# altair.net
KiCad netlist of a schematic drawn in EAGLE
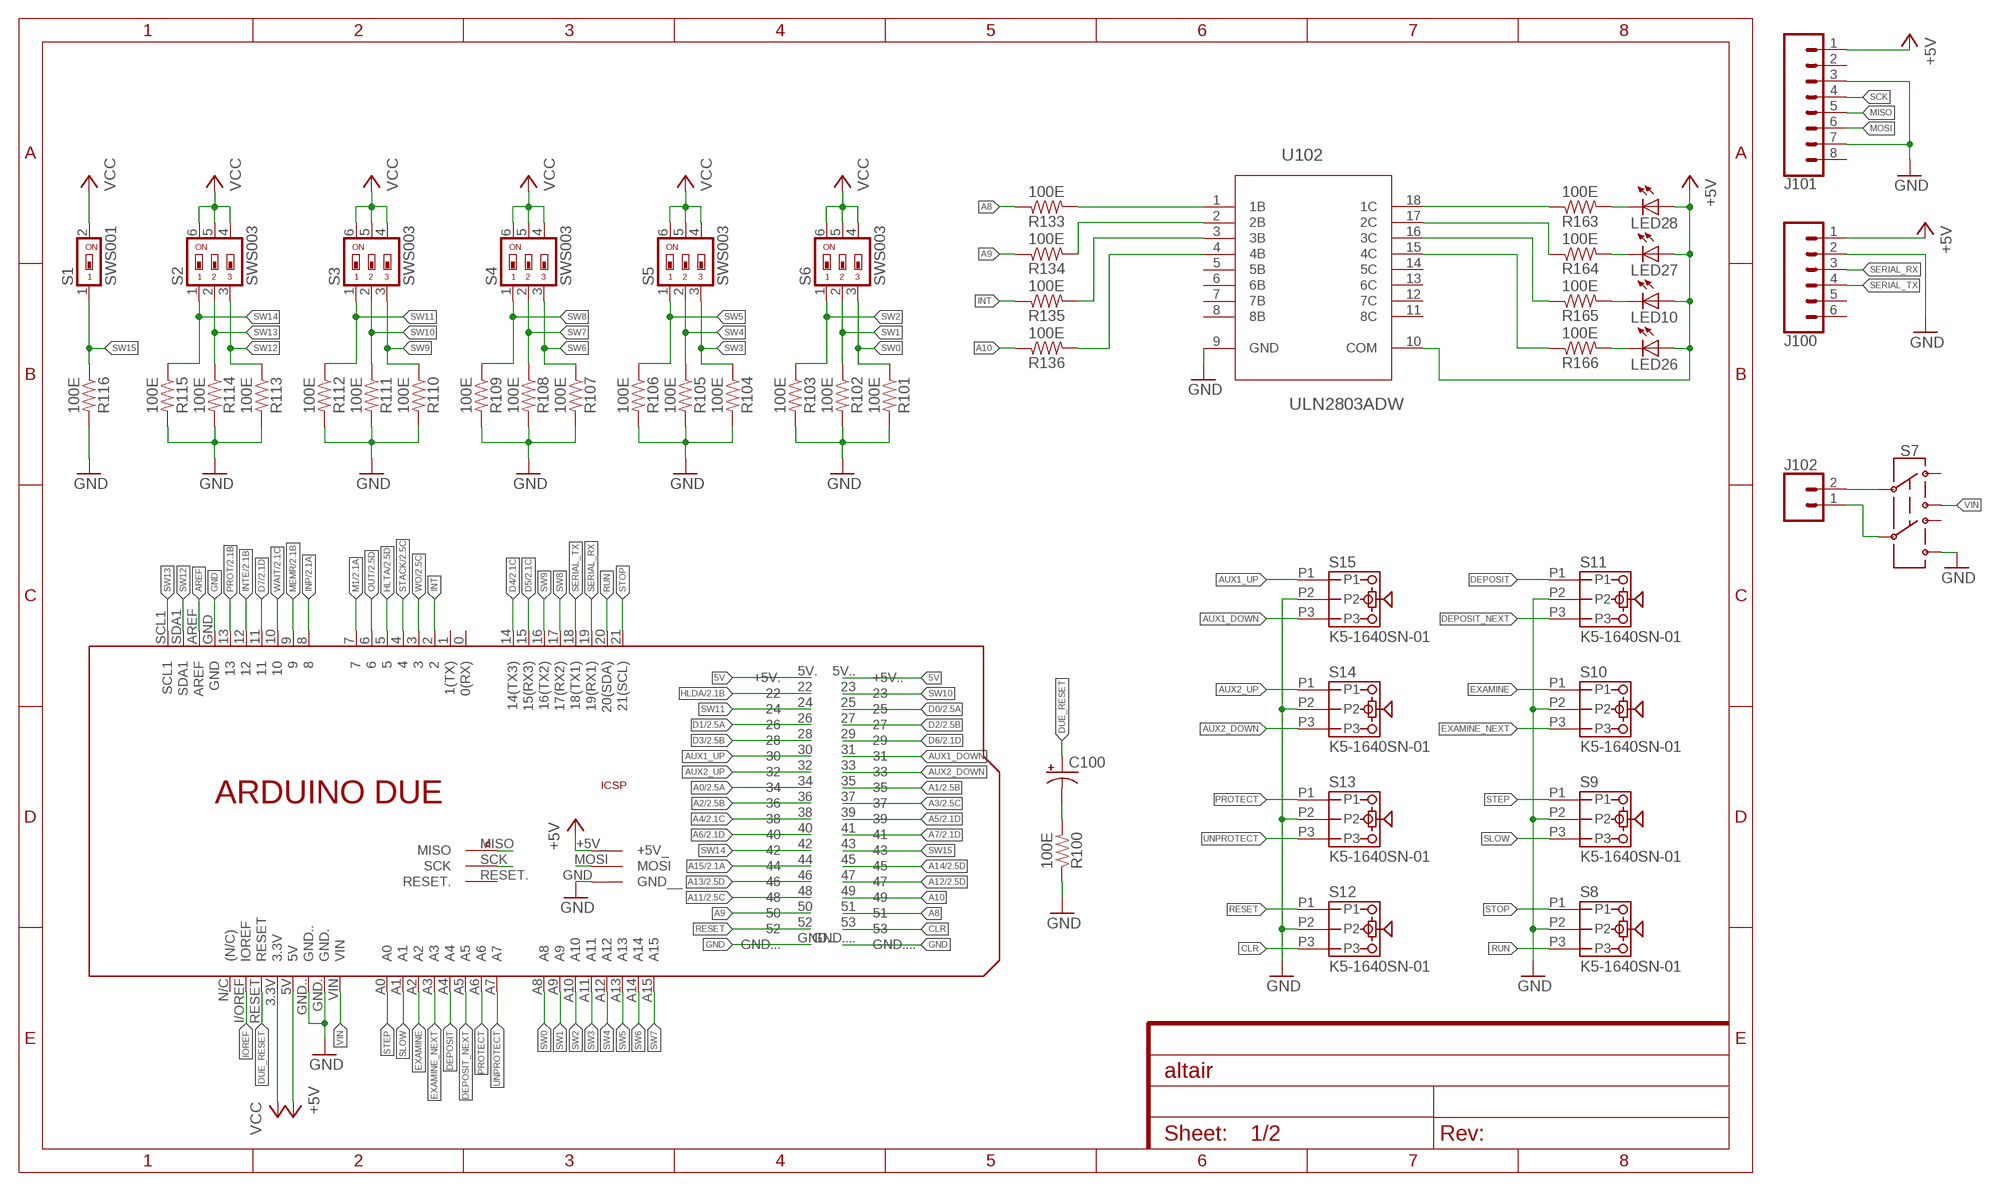
[diagram p0: schematic, sheet 1]
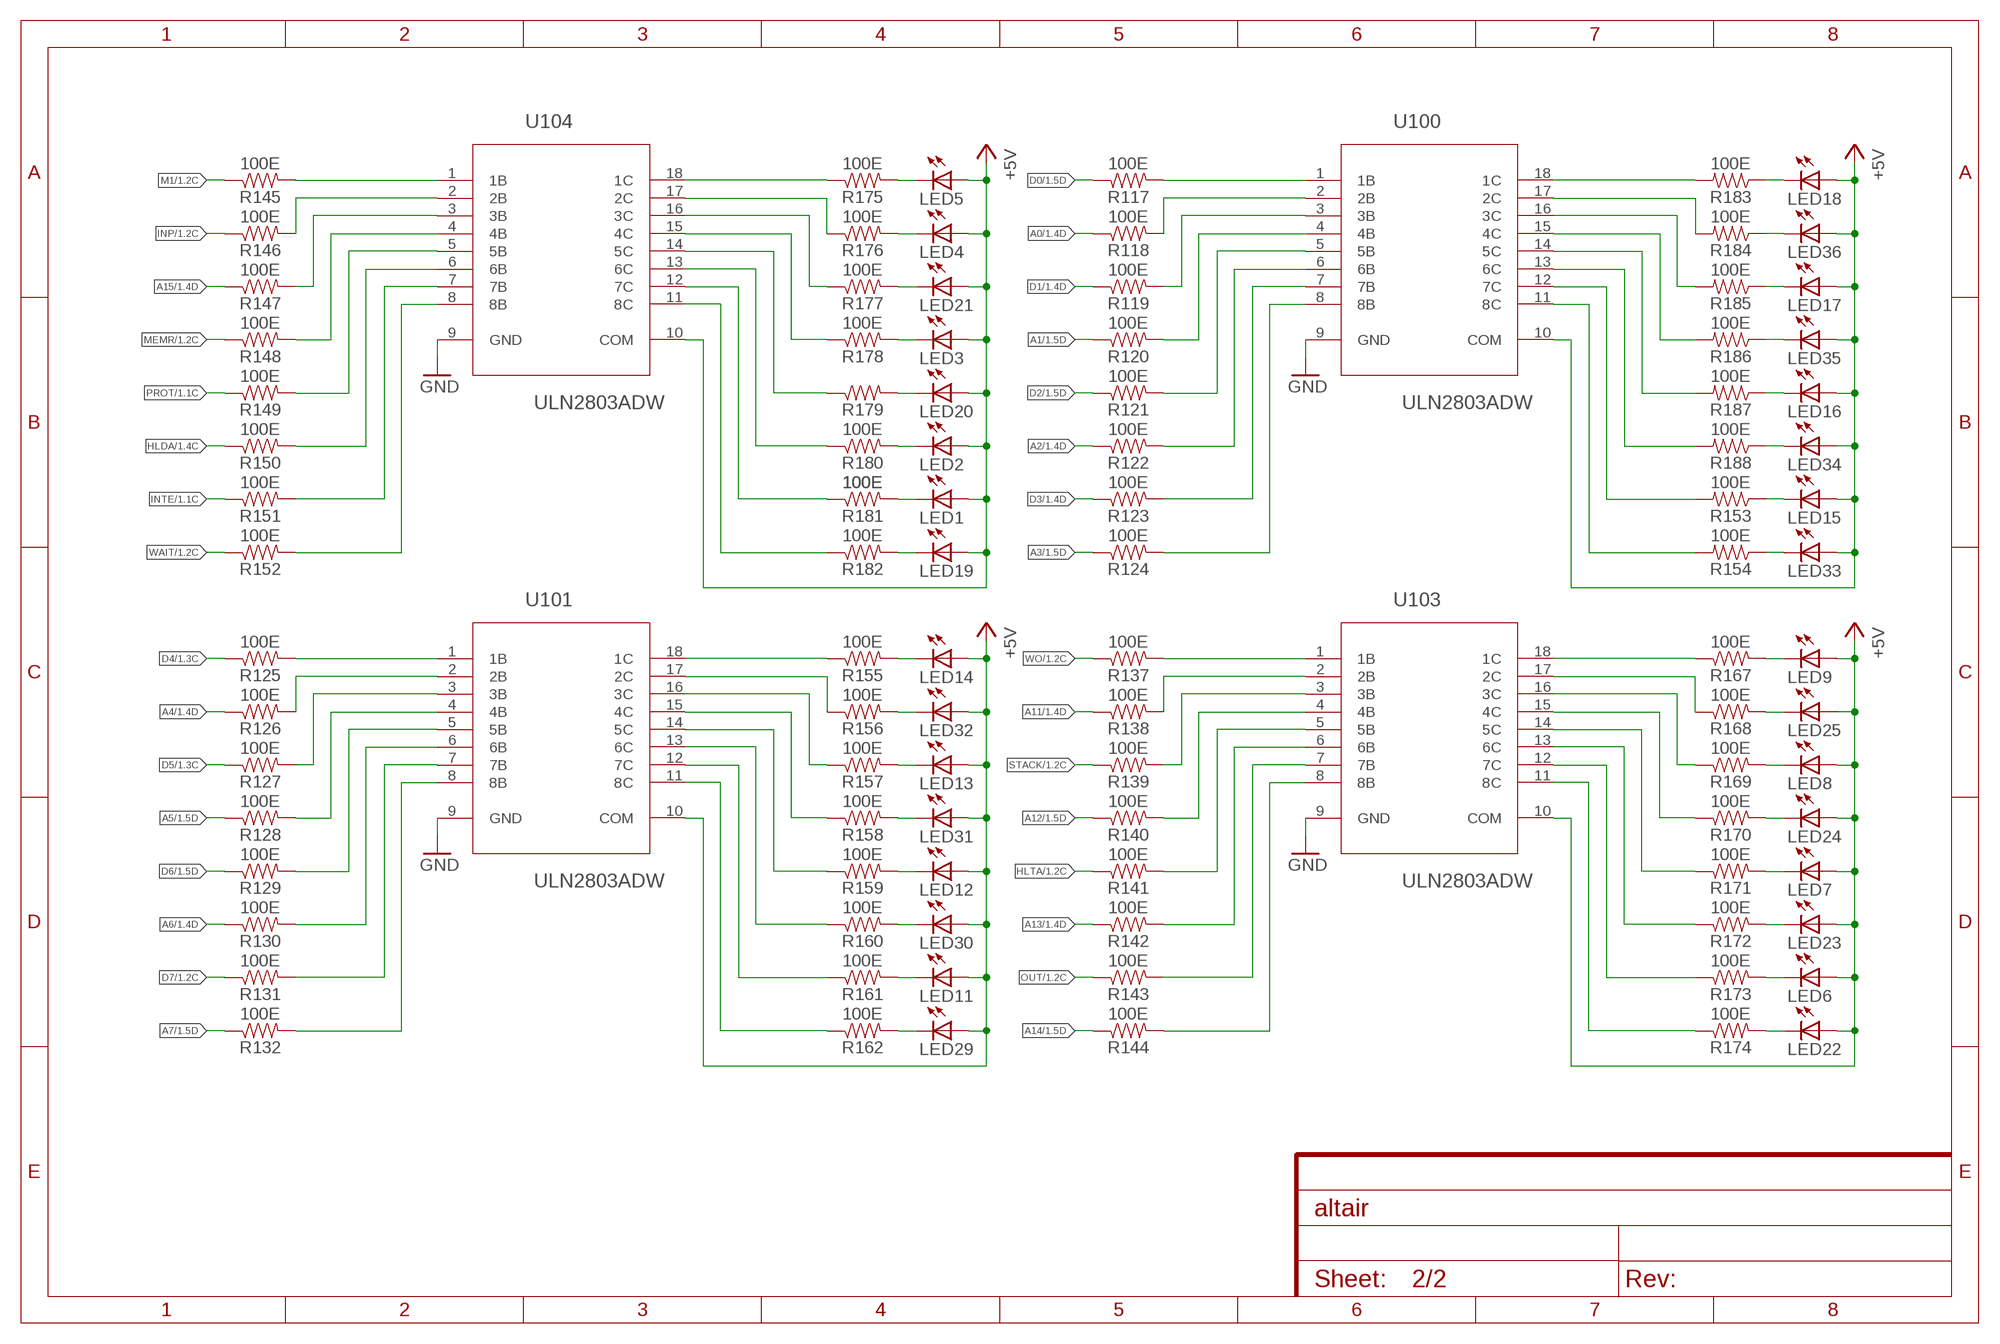
[diagram p1: schematic, sheet 2]

(export (version "E")
  (design (tool "Eeschema 10.0.6"))
  (components
    (comp (ref "C100")
      (value "CPOL-USD")
      (footprint "eagle-import:PANASONIC_D")
      (libsource (lib "eagle-import") (part "CPOL-USD"))
    )
    (comp (ref "J100")
      (value "CONN_06LOCK")
      (footprint "eagle-import:1X06_LOCK")
      (libsource (lib "eagle-import") (part "CONN_06LOCK"))
    )
    (comp (ref "J101")
      (value "CONN_08LOCK")
      (footprint "eagle-import:1X08_LOCK")
      (libsource (lib "eagle-import") (part "CONN_08LOCK"))
    )
    (comp (ref "J102")
      (value "CONN_02POLAR_LOCK")
      (footprint "eagle-import:MOLEX-1X2_LOCK")
      (libsource (lib "eagle-import") (part "CONN_02POLAR_LOCK"))
    )
    (comp (ref "LED10")
      (value "LEDCHIP-LED0805")
      (footprint "eagle-import:CHIP-LED0805")
      (libsource (lib "eagle-import") (part "LEDCHIP-LED0805"))
    )
    (comp (ref "LED26")
      (value "LEDCHIP-LED0805")
      (footprint "eagle-import:CHIP-LED0805")
      (libsource (lib "eagle-import") (part "LEDCHIP-LED0805"))
    )
    (comp (ref "LED27")
      (value "LEDCHIP-LED0805")
      (footprint "eagle-import:CHIP-LED0805")
      (libsource (lib "eagle-import") (part "LEDCHIP-LED0805"))
    )
    (comp (ref "LED28")
      (value "LEDCHIP-LED0805")
      (footprint "eagle-import:CHIP-LED0805")
      (libsource (lib "eagle-import") (part "LEDCHIP-LED0805"))
    )
    (comp (ref "PCB1")
      (value "ARDUINO_DUEARDUINO_DUE")
      (footprint "eagle-import:ARDUINO_MEGA2560")
      (libsource (lib "eagle-import") (part "ARDUINO_DUEARDUINO_DUE"))
    )
    (comp (ref "R100")
      (value "100E")
      (footprint "eagle-import:0805")
      (libsource (lib "eagle-import") (part "RESISTOR0805"))
    )
    (comp (ref "R101")
      (value "100E")
      (footprint "eagle-import:0805")
      (libsource (lib "eagle-import") (part "RESISTOR0805"))
    )
    (comp (ref "R102")
      (value "100E")
      (footprint "eagle-import:0805")
      (libsource (lib "eagle-import") (part "RESISTOR0805"))
    )
    (comp (ref "R103")
      (value "100E")
      (footprint "eagle-import:0805")
      (libsource (lib "eagle-import") (part "RESISTOR0805"))
    )
    (comp (ref "R104")
      (value "100E")
      (footprint "eagle-import:0805")
      (libsource (lib "eagle-import") (part "RESISTOR0805"))
    )
    (comp (ref "R105")
      (value "100E")
      (footprint "eagle-import:0805")
      (libsource (lib "eagle-import") (part "RESISTOR0805"))
    )
    (comp (ref "R106")
      (value "100E")
      (footprint "eagle-import:0805")
      (libsource (lib "eagle-import") (part "RESISTOR0805"))
    )
    (comp (ref "R107")
      (value "100E")
      (footprint "eagle-import:0805")
      (libsource (lib "eagle-import") (part "RESISTOR0805"))
    )
    (comp (ref "R108")
      (value "100E")
      (footprint "eagle-import:0805")
      (libsource (lib "eagle-import") (part "RESISTOR0805"))
    )
    (comp (ref "R109")
      (value "100E")
      (footprint "eagle-import:0805")
      (libsource (lib "eagle-import") (part "RESISTOR0805"))
    )
    (comp (ref "R110")
      (value "100E")
      (footprint "eagle-import:0805")
      (libsource (lib "eagle-import") (part "RESISTOR0805"))
    )
    (comp (ref "R111")
      (value "100E")
      (footprint "eagle-import:0805")
      (libsource (lib "eagle-import") (part "RESISTOR0805"))
    )
    (comp (ref "R112")
      (value "100E")
      (footprint "eagle-import:0805")
      (libsource (lib "eagle-import") (part "RESISTOR0805"))
    )
    (comp (ref "R113")
      (value "100E")
      (footprint "eagle-import:0805")
      (libsource (lib "eagle-import") (part "RESISTOR0805"))
    )
    (comp (ref "R114")
      (value "100E")
      (footprint "eagle-import:0805")
      (libsource (lib "eagle-import") (part "RESISTOR0805"))
    )
    (comp (ref "R115")
      (value "100E")
      (footprint "eagle-import:0805")
      (libsource (lib "eagle-import") (part "RESISTOR0805"))
    )
    (comp (ref "R116")
      (value "100E")
      (footprint "eagle-import:0805")
      (libsource (lib "eagle-import") (part "RESISTOR0805"))
    )
    (comp (ref "R133")
      (value "100E")
      (footprint "eagle-import:0805")
      (libsource (lib "eagle-import") (part "RESISTOR0805"))
    )
    (comp (ref "R134")
      (value "100E")
      (footprint "eagle-import:0805")
      (libsource (lib "eagle-import") (part "RESISTOR0805"))
    )
    (comp (ref "R135")
      (value "100E")
      (footprint "eagle-import:0805")
      (libsource (lib "eagle-import") (part "RESISTOR0805"))
    )
    (comp (ref "R136")
      (value "100E")
      (footprint "eagle-import:0805")
      (libsource (lib "eagle-import") (part "RESISTOR0805"))
    )
    (comp (ref "R163")
      (value "100E")
      (footprint "eagle-import:0805")
      (libsource (lib "eagle-import") (part "RESISTOR0805"))
    )
    (comp (ref "R164")
      (value "100E")
      (footprint "eagle-import:0805")
      (libsource (lib "eagle-import") (part "RESISTOR0805"))
    )
    (comp (ref "R165")
      (value "100E")
      (footprint "eagle-import:0805")
      (libsource (lib "eagle-import") (part "RESISTOR0805"))
    )
    (comp (ref "R166")
      (value "100E")
      (footprint "eagle-import:0805")
      (libsource (lib "eagle-import") (part "RESISTOR0805"))
    )
    (comp (ref "S1")
      (value "SWS001")
      (footprint "eagle-import:SMS-001")
      (libsource (lib "eagle-import") (part "SWS001"))
    )
    (comp (ref "S2")
      (value "SWS003")
      (footprint "eagle-import:SMS-003")
      (libsource (lib "eagle-import") (part "SWS003"))
    )
    (comp (ref "S3")
      (value "SWS003")
      (footprint "eagle-import:SMS-003")
      (libsource (lib "eagle-import") (part "SWS003"))
    )
    (comp (ref "S4")
      (value "SWS003")
      (footprint "eagle-import:SMS-003")
      (libsource (lib "eagle-import") (part "SWS003"))
    )
    (comp (ref "S5")
      (value "SWS003")
      (footprint "eagle-import:SMS-003")
      (libsource (lib "eagle-import") (part "SWS003"))
    )
    (comp (ref "S6")
      (value "SWS003")
      (footprint "eagle-import:SMS-003")
      (libsource (lib "eagle-import") (part "SWS003"))
    )
    (comp (ref "S7")
      (value "SWITCH-DPDT-SMD-AYZ0202")
      (footprint "eagle-import:SWITCH_DPDT_SMD_AYZ0202")
      (libsource (lib "eagle-import") (part "SWITCH-DPDT-SMD-AYZ0202"))
    )
    (comp (ref "S8")
      (value "K5-1640SN-01")
      (footprint "eagle-import:K5-1640SN-01")
      (libsource (lib "eagle-import") (part "K5-1640SN-01"))
    )
    (comp (ref "S9")
      (value "K5-1640SN-01")
      (footprint "eagle-import:K5-1640SN-01")
      (libsource (lib "eagle-import") (part "K5-1640SN-01"))
    )
    (comp (ref "S10")
      (value "K5-1640SN-01")
      (footprint "eagle-import:K5-1640SN-01")
      (libsource (lib "eagle-import") (part "K5-1640SN-01"))
    )
    (comp (ref "S11")
      (value "K5-1640SN-01")
      (footprint "eagle-import:K5-1640SN-01")
      (libsource (lib "eagle-import") (part "K5-1640SN-01"))
    )
    (comp (ref "S12")
      (value "K5-1640SN-01")
      (footprint "eagle-import:K5-1640SN-01")
      (libsource (lib "eagle-import") (part "K5-1640SN-01"))
    )
    (comp (ref "S13")
      (value "K5-1640SN-01")
      (footprint "eagle-import:K5-1640SN-01")
      (libsource (lib "eagle-import") (part "K5-1640SN-01"))
    )
    (comp (ref "S14")
      (value "K5-1640SN-01")
      (footprint "eagle-import:K5-1640SN-01")
      (libsource (lib "eagle-import") (part "K5-1640SN-01"))
    )
    (comp (ref "S15")
      (value "K5-1640SN-01")
      (footprint "eagle-import:K5-1640SN-01")
      (libsource (lib "eagle-import") (part "K5-1640SN-01"))
    )
    (comp (ref "U102")
      (value "ULN2803ADW")
      (footprint "eagle-import:SOIC127P1030X265-18N")
      (libsource (lib "eagle-import") (part "ULN2803ADW"))
    )
    (comp (ref "LED1")
      (value "LEDCHIP-LED0805")
      (footprint "eagle-import:CHIP-LED0805")
      (libsource (lib "eagle-import") (part "LEDCHIP-LED0805"))
    )
    (comp (ref "LED2")
      (value "LEDCHIP-LED0805")
      (footprint "eagle-import:CHIP-LED0805")
      (libsource (lib "eagle-import") (part "LEDCHIP-LED0805"))
    )
    (comp (ref "LED3")
      (value "LEDCHIP-LED0805")
      (footprint "eagle-import:CHIP-LED0805")
      (libsource (lib "eagle-import") (part "LEDCHIP-LED0805"))
    )
    (comp (ref "LED4")
      (value "LEDCHIP-LED0805")
      (footprint "eagle-import:CHIP-LED0805")
      (libsource (lib "eagle-import") (part "LEDCHIP-LED0805"))
    )
    (comp (ref "LED5")
      (value "LEDCHIP-LED0805")
      (footprint "eagle-import:CHIP-LED0805")
      (libsource (lib "eagle-import") (part "LEDCHIP-LED0805"))
    )
    (comp (ref "LED6")
      (value "LEDCHIP-LED0805")
      (footprint "eagle-import:CHIP-LED0805")
      (libsource (lib "eagle-import") (part "LEDCHIP-LED0805"))
    )
    (comp (ref "LED7")
      (value "LEDCHIP-LED0805")
      (footprint "eagle-import:CHIP-LED0805")
      (libsource (lib "eagle-import") (part "LEDCHIP-LED0805"))
    )
    (comp (ref "LED8")
      (value "LEDCHIP-LED0805")
      (footprint "eagle-import:CHIP-LED0805")
      (libsource (lib "eagle-import") (part "LEDCHIP-LED0805"))
    )
    (comp (ref "LED9")
      (value "LEDCHIP-LED0805")
      (footprint "eagle-import:CHIP-LED0805")
      (libsource (lib "eagle-import") (part "LEDCHIP-LED0805"))
    )
    (comp (ref "LED11")
      (value "LEDCHIP-LED0805")
      (footprint "eagle-import:CHIP-LED0805")
      (libsource (lib "eagle-import") (part "LEDCHIP-LED0805"))
    )
    (comp (ref "LED12")
      (value "LEDCHIP-LED0805")
      (footprint "eagle-import:CHIP-LED0805")
      (libsource (lib "eagle-import") (part "LEDCHIP-LED0805"))
    )
    (comp (ref "LED13")
      (value "LEDCHIP-LED0805")
      (footprint "eagle-import:CHIP-LED0805")
      (libsource (lib "eagle-import") (part "LEDCHIP-LED0805"))
    )
    (comp (ref "LED14")
      (value "LEDCHIP-LED0805")
      (footprint "eagle-import:CHIP-LED0805")
      (libsource (lib "eagle-import") (part "LEDCHIP-LED0805"))
    )
    (comp (ref "LED15")
      (value "LEDCHIP-LED0805")
      (footprint "eagle-import:CHIP-LED0805")
      (libsource (lib "eagle-import") (part "LEDCHIP-LED0805"))
    )
    (comp (ref "LED16")
      (value "LEDCHIP-LED0805")
      (footprint "eagle-import:CHIP-LED0805")
      (libsource (lib "eagle-import") (part "LEDCHIP-LED0805"))
    )
    (comp (ref "LED17")
      (value "LEDCHIP-LED0805")
      (footprint "eagle-import:CHIP-LED0805")
      (libsource (lib "eagle-import") (part "LEDCHIP-LED0805"))
    )
    (comp (ref "LED18")
      (value "LEDCHIP-LED0805")
      (footprint "eagle-import:CHIP-LED0805")
      (libsource (lib "eagle-import") (part "LEDCHIP-LED0805"))
    )
    (comp (ref "LED19")
      (value "LEDCHIP-LED0805")
      (footprint "eagle-import:CHIP-LED0805")
      (libsource (lib "eagle-import") (part "LEDCHIP-LED0805"))
    )
    (comp (ref "LED20")
      (value "LEDCHIP-LED0805")
      (footprint "eagle-import:CHIP-LED0805")
      (libsource (lib "eagle-import") (part "LEDCHIP-LED0805"))
    )
    (comp (ref "LED21")
      (value "LEDCHIP-LED0805")
      (footprint "eagle-import:CHIP-LED0805")
      (libsource (lib "eagle-import") (part "LEDCHIP-LED0805"))
    )
    (comp (ref "LED22")
      (value "LEDCHIP-LED0805")
      (footprint "eagle-import:CHIP-LED0805")
      (libsource (lib "eagle-import") (part "LEDCHIP-LED0805"))
    )
    (comp (ref "LED23")
      (value "LEDCHIP-LED0805")
      (footprint "eagle-import:CHIP-LED0805")
      (libsource (lib "eagle-import") (part "LEDCHIP-LED0805"))
    )
    (comp (ref "LED24")
      (value "LEDCHIP-LED0805")
      (footprint "eagle-import:CHIP-LED0805")
      (libsource (lib "eagle-import") (part "LEDCHIP-LED0805"))
    )
    (comp (ref "LED25")
      (value "LEDCHIP-LED0805")
      (footprint "eagle-import:CHIP-LED0805")
      (libsource (lib "eagle-import") (part "LEDCHIP-LED0805"))
    )
    (comp (ref "LED29")
      (value "LEDCHIP-LED0805")
      (footprint "eagle-import:CHIP-LED0805")
      (libsource (lib "eagle-import") (part "LEDCHIP-LED0805"))
    )
    (comp (ref "LED30")
      (value "LEDCHIP-LED0805")
      (footprint "eagle-import:CHIP-LED0805")
      (libsource (lib "eagle-import") (part "LEDCHIP-LED0805"))
    )
    (comp (ref "LED31")
      (value "LEDCHIP-LED0805")
      (footprint "eagle-import:CHIP-LED0805")
      (libsource (lib "eagle-import") (part "LEDCHIP-LED0805"))
    )
    (comp (ref "LED32")
      (value "LEDCHIP-LED0805")
      (footprint "eagle-import:CHIP-LED0805")
      (libsource (lib "eagle-import") (part "LEDCHIP-LED0805"))
    )
    (comp (ref "LED33")
      (value "LEDCHIP-LED0805")
      (footprint "eagle-import:CHIP-LED0805")
      (libsource (lib "eagle-import") (part "LEDCHIP-LED0805"))
    )
    (comp (ref "LED34")
      (value "LEDCHIP-LED0805")
      (footprint "eagle-import:CHIP-LED0805")
      (libsource (lib "eagle-import") (part "LEDCHIP-LED0805"))
    )
    (comp (ref "LED35")
      (value "LEDCHIP-LED0805")
      (footprint "eagle-import:CHIP-LED0805")
      (libsource (lib "eagle-import") (part "LEDCHIP-LED0805"))
    )
    (comp (ref "LED36")
      (value "LEDCHIP-LED0805")
      (footprint "eagle-import:CHIP-LED0805")
      (libsource (lib "eagle-import") (part "LEDCHIP-LED0805"))
    )
    (comp (ref "R117")
      (value "100E")
      (footprint "eagle-import:0805")
      (libsource (lib "eagle-import") (part "RESISTOR0805"))
    )
    (comp (ref "R118")
      (value "100E")
      (footprint "eagle-import:0805")
      (libsource (lib "eagle-import") (part "RESISTOR0805"))
    )
    (comp (ref "R119")
      (value "100E")
      (footprint "eagle-import:0805")
      (libsource (lib "eagle-import") (part "RESISTOR0805"))
    )
    (comp (ref "R120")
      (value "100E")
      (footprint "eagle-import:0805")
      (libsource (lib "eagle-import") (part "RESISTOR0805"))
    )
    (comp (ref "R121")
      (value "100E")
      (footprint "eagle-import:0805")
      (libsource (lib "eagle-import") (part "RESISTOR0805"))
    )
    (comp (ref "R122")
      (value "100E")
      (footprint "eagle-import:0805")
      (libsource (lib "eagle-import") (part "RESISTOR0805"))
    )
    (comp (ref "R123")
      (value "100E")
      (footprint "eagle-import:0805")
      (libsource (lib "eagle-import") (part "RESISTOR0805"))
    )
    (comp (ref "R124")
      (value "100E")
      (footprint "eagle-import:0805")
      (libsource (lib "eagle-import") (part "RESISTOR0805"))
    )
    (comp (ref "R125")
      (value "100E")
      (footprint "eagle-import:0805")
      (libsource (lib "eagle-import") (part "RESISTOR0805"))
    )
    (comp (ref "R126")
      (value "100E")
      (footprint "eagle-import:0805")
      (libsource (lib "eagle-import") (part "RESISTOR0805"))
    )
    (comp (ref "R127")
      (value "100E")
      (footprint "eagle-import:0805")
      (libsource (lib "eagle-import") (part "RESISTOR0805"))
    )
    (comp (ref "R128")
      (value "100E")
      (footprint "eagle-import:0805")
      (libsource (lib "eagle-import") (part "RESISTOR0805"))
    )
    (comp (ref "R129")
      (value "100E")
      (footprint "eagle-import:0805")
      (libsource (lib "eagle-import") (part "RESISTOR0805"))
    )
    (comp (ref "R130")
      (value "100E")
      (footprint "eagle-import:0805")
      (libsource (lib "eagle-import") (part "RESISTOR0805"))
    )
    (comp (ref "R131")
      (value "100E")
      (footprint "eagle-import:0805")
      (libsource (lib "eagle-import") (part "RESISTOR0805"))
    )
    (comp (ref "R132")
      (value "100E")
      (footprint "eagle-import:0805")
      (libsource (lib "eagle-import") (part "RESISTOR0805"))
    )
    (comp (ref "R137")
      (value "100E")
      (footprint "eagle-import:0805")
      (libsource (lib "eagle-import") (part "RESISTOR0805"))
    )
    (comp (ref "R138")
      (value "100E")
      (footprint "eagle-import:0805")
      (libsource (lib "eagle-import") (part "RESISTOR0805"))
    )
    (comp (ref "R139")
      (value "100E")
      (footprint "eagle-import:0805")
      (libsource (lib "eagle-import") (part "RESISTOR0805"))
    )
    (comp (ref "R140")
      (value "100E")
      (footprint "eagle-import:0805")
      (libsource (lib "eagle-import") (part "RESISTOR0805"))
    )
    (comp (ref "R141")
      (value "100E")
      (footprint "eagle-import:0805")
      (libsource (lib "eagle-import") (part "RESISTOR0805"))
    )
    (comp (ref "R142")
      (value "100E")
      (footprint "eagle-import:0805")
      (libsource (lib "eagle-import") (part "RESISTOR0805"))
    )
    (comp (ref "R143")
      (value "100E")
      (footprint "eagle-import:0805")
      (libsource (lib "eagle-import") (part "RESISTOR0805"))
    )
    (comp (ref "R144")
      (value "100E")
      (footprint "eagle-import:0805")
      (libsource (lib "eagle-import") (part "RESISTOR0805"))
    )
    (comp (ref "R145")
      (value "100E")
      (footprint "eagle-import:0805")
      (libsource (lib "eagle-import") (part "RESISTOR0805"))
    )
    (comp (ref "R146")
      (value "100E")
      (footprint "eagle-import:0805")
      (libsource (lib "eagle-import") (part "RESISTOR0805"))
    )
    (comp (ref "R147")
      (value "100E")
      (footprint "eagle-import:0805")
      (libsource (lib "eagle-import") (part "RESISTOR0805"))
    )
    (comp (ref "R148")
      (value "100E")
      (footprint "eagle-import:0805")
      (libsource (lib "eagle-import") (part "RESISTOR0805"))
    )
    (comp (ref "R149")
      (value "100E")
      (footprint "eagle-import:0805")
      (libsource (lib "eagle-import") (part "RESISTOR0805"))
    )
    (comp (ref "R150")
      (value "100E")
      (footprint "eagle-import:0805")
      (libsource (lib "eagle-import") (part "RESISTOR0805"))
    )
    (comp (ref "R151")
      (value "100E")
      (footprint "eagle-import:0805")
      (libsource (lib "eagle-import") (part "RESISTOR0805"))
    )
    (comp (ref "R152")
      (value "100E")
      (footprint "eagle-import:0805")
      (libsource (lib "eagle-import") (part "RESISTOR0805"))
    )
    (comp (ref "R153")
      (value "100E")
      (footprint "eagle-import:0805")
      (libsource (lib "eagle-import") (part "RESISTOR0805"))
    )
    (comp (ref "R154")
      (value "100E")
      (footprint "eagle-import:0805")
      (libsource (lib "eagle-import") (part "RESISTOR0805"))
    )
    (comp (ref "R155")
      (value "100E")
      (footprint "eagle-import:0805")
      (libsource (lib "eagle-import") (part "RESISTOR0805"))
    )
    (comp (ref "R156")
      (value "100E")
      (footprint "eagle-import:0805")
      (libsource (lib "eagle-import") (part "RESISTOR0805"))
    )
    (comp (ref "R157")
      (value "100E")
      (footprint "eagle-import:0805")
      (libsource (lib "eagle-import") (part "RESISTOR0805"))
    )
    (comp (ref "R158")
      (value "100E")
      (footprint "eagle-import:0805")
      (libsource (lib "eagle-import") (part "RESISTOR0805"))
    )
    (comp (ref "R159")
      (value "100E")
      (footprint "eagle-import:0805")
      (libsource (lib "eagle-import") (part "RESISTOR0805"))
    )
    (comp (ref "R160")
      (value "100E")
      (footprint "eagle-import:0805")
      (libsource (lib "eagle-import") (part "RESISTOR0805"))
    )
    (comp (ref "R161")
      (value "100E")
      (footprint "eagle-import:0805")
      (libsource (lib "eagle-import") (part "RESISTOR0805"))
    )
    (comp (ref "R162")
      (value "100E")
      (footprint "eagle-import:0805")
      (libsource (lib "eagle-import") (part "RESISTOR0805"))
    )
    (comp (ref "R167")
      (value "100E")
      (footprint "eagle-import:0805")
      (libsource (lib "eagle-import") (part "RESISTOR0805"))
    )
    (comp (ref "R168")
      (value "100E")
      (footprint "eagle-import:0805")
      (libsource (lib "eagle-import") (part "RESISTOR0805"))
    )
    (comp (ref "R169")
      (value "100E")
      (footprint "eagle-import:0805")
      (libsource (lib "eagle-import") (part "RESISTOR0805"))
    )
    (comp (ref "R170")
      (value "100E")
      (footprint "eagle-import:0805")
      (libsource (lib "eagle-import") (part "RESISTOR0805"))
    )
    (comp (ref "R171")
      (value "100E")
      (footprint "eagle-import:0805")
      (libsource (lib "eagle-import") (part "RESISTOR0805"))
    )
    (comp (ref "R172")
      (value "100E")
      (footprint "eagle-import:0805")
      (libsource (lib "eagle-import") (part "RESISTOR0805"))
    )
    (comp (ref "R173")
      (value "100E")
      (footprint "eagle-import:0805")
      (libsource (lib "eagle-import") (part "RESISTOR0805"))
    )
    (comp (ref "R174")
      (value "100E")
      (footprint "eagle-import:0805")
      (libsource (lib "eagle-import") (part "RESISTOR0805"))
    )
    (comp (ref "R175")
      (value "100E")
      (footprint "eagle-import:0805")
      (libsource (lib "eagle-import") (part "RESISTOR0805"))
    )
    (comp (ref "R176")
      (value "100E")
      (footprint "eagle-import:0805")
      (libsource (lib "eagle-import") (part "RESISTOR0805"))
    )
    (comp (ref "R177")
      (value "100E")
      (footprint "eagle-import:0805")
      (libsource (lib "eagle-import") (part "RESISTOR0805"))
    )
    (comp (ref "R178")
      (value "100E")
      (footprint "eagle-import:0805")
      (libsource (lib "eagle-import") (part "RESISTOR0805"))
    )
    (comp (ref "R179")
      (value "100E")
      (footprint "eagle-import:0805")
      (libsource (lib "eagle-import") (part "RESISTOR0805"))
    )
    (comp (ref "R180")
      (value "100E")
      (footprint "eagle-import:0805")
      (libsource (lib "eagle-import") (part "RESISTOR0805"))
    )
    (comp (ref "R181")
      (value "100E")
      (footprint "eagle-import:0805")
      (libsource (lib "eagle-import") (part "RESISTOR0805"))
    )
    (comp (ref "R182")
      (value "100E")
      (footprint "eagle-import:0805")
      (libsource (lib "eagle-import") (part "RESISTOR0805"))
    )
    (comp (ref "R183")
      (value "100E")
      (footprint "eagle-import:0805")
      (libsource (lib "eagle-import") (part "RESISTOR0805"))
    )
    (comp (ref "R184")
      (value "100E")
      (footprint "eagle-import:0805")
      (libsource (lib "eagle-import") (part "RESISTOR0805"))
    )
    (comp (ref "R185")
      (value "100E")
      (footprint "eagle-import:0805")
      (libsource (lib "eagle-import") (part "RESISTOR0805"))
    )
    (comp (ref "R186")
      (value "100E")
      (footprint "eagle-import:0805")
      (libsource (lib "eagle-import") (part "RESISTOR0805"))
    )
    (comp (ref "R187")
      (value "100E")
      (footprint "eagle-import:0805")
      (libsource (lib "eagle-import") (part "RESISTOR0805"))
    )
    (comp (ref "R188")
      (value "100E")
      (footprint "eagle-import:0805")
      (libsource (lib "eagle-import") (part "RESISTOR0805"))
    )
    (comp (ref "U100")
      (value "ULN2803ADW")
      (footprint "eagle-import:SOIC127P1030X265-18N")
      (libsource (lib "eagle-import") (part "ULN2803ADW"))
    )
    (comp (ref "U101")
      (value "ULN2803ADW")
      (footprint "eagle-import:SOIC127P1030X265-18N")
      (libsource (lib "eagle-import") (part "ULN2803ADW"))
    )
    (comp (ref "U103")
      (value "ULN2803ADW")
      (footprint "eagle-import:SOIC127P1030X265-18N")
      (libsource (lib "eagle-import") (part "ULN2803ADW"))
    )
    (comp (ref "U104")
      (value "ULN2803ADW")
      (footprint "eagle-import:SOIC127P1030X265-18N")
      (libsource (lib "eagle-import") (part "ULN2803ADW"))
    )
  )
  (nets
    (net (code "1") (name "+5V") (class "Default")
      (node (ref "J100") (pin "1") (pinfunction "1_1") (pintype "passive"))
      (node (ref "J101") (pin "1") (pinfunction "1_1") (pintype "passive"))
      (node (ref "LED1") (pin "A") (pinfunction "A_A") (pintype "passive"))
      (node (ref "LED10") (pin "A") (pinfunction "A_A") (pintype "passive"))
      (node (ref "LED11") (pin "A") (pinfunction "A_A") (pintype "passive"))
      (node (ref "LED12") (pin "A") (pinfunction "A_A") (pintype "passive"))
      (node (ref "LED13") (pin "A") (pinfunction "A_A") (pintype "passive"))
      (node (ref "LED14") (pin "A") (pinfunction "A_A") (pintype "passive"))
      (node (ref "LED15") (pin "A") (pinfunction "A_A") (pintype "passive"))
      (node (ref "LED16") (pin "A") (pinfunction "A_A") (pintype "passive"))
      (node (ref "LED17") (pin "A") (pinfunction "A_A") (pintype "passive"))
      (node (ref "LED18") (pin "A") (pinfunction "A_A") (pintype "passive"))
      (node (ref "LED19") (pin "A") (pinfunction "A_A") (pintype "passive"))
      (node (ref "LED2") (pin "A") (pinfunction "A_A") (pintype "passive"))
      (node (ref "LED20") (pin "A") (pinfunction "A_A") (pintype "passive"))
      (node (ref "LED21") (pin "A") (pinfunction "A_A") (pintype "passive"))
      (node (ref "LED22") (pin "A") (pinfunction "A_A") (pintype "passive"))
      (node (ref "LED23") (pin "A") (pinfunction "A_A") (pintype "passive"))
      (node (ref "LED24") (pin "A") (pinfunction "A_A") (pintype "passive"))
      (node (ref "LED25") (pin "A") (pinfunction "A_A") (pintype "passive"))
      (node (ref "LED26") (pin "A") (pinfunction "A_A") (pintype "passive"))
      (node (ref "LED27") (pin "A") (pinfunction "A_A") (pintype "passive"))
      (node (ref "LED28") (pin "A") (pinfunction "A_A") (pintype "passive"))
      (node (ref "LED29") (pin "A") (pinfunction "A_A") (pintype "passive"))
      (node (ref "LED3") (pin "A") (pinfunction "A_A") (pintype "passive"))
      (node (ref "LED30") (pin "A") (pinfunction "A_A") (pintype "passive"))
      (node (ref "LED31") (pin "A") (pinfunction "A_A") (pintype "passive"))
      (node (ref "LED32") (pin "A") (pinfunction "A_A") (pintype "passive"))
      (node (ref "LED33") (pin "A") (pinfunction "A_A") (pintype "passive"))
      (node (ref "LED34") (pin "A") (pinfunction "A_A") (pintype "passive"))
      (node (ref "LED35") (pin "A") (pinfunction "A_A") (pintype "passive"))
      (node (ref "LED36") (pin "A") (pinfunction "A_A") (pintype "passive"))
      (node (ref "LED4") (pin "A") (pinfunction "A_A") (pintype "passive"))
      (node (ref "LED5") (pin "A") (pinfunction "A_A") (pintype "passive"))
      (node (ref "LED6") (pin "A") (pinfunction "A_A") (pintype "passive"))
      (node (ref "LED7") (pin "A") (pinfunction "A_A") (pintype "passive"))
      (node (ref "LED8") (pin "A") (pinfunction "A_A") (pintype "passive"))
      (node (ref "LED9") (pin "A") (pinfunction "A_A") (pintype "passive"))
      (node (ref "PCB1") (pin "+5V_") (pinfunction "+5V__+5V_") (pintype "bidirectional"))
      (node (ref "PCB1") (pin "5V") (pinfunction "5V_5V") (pintype "bidirectional"))
      (node (ref "U100") (pin "10") (pinfunction "COM_10") (pintype "output"))
      (node (ref "U101") (pin "10") (pinfunction "COM_10") (pintype "output"))
      (node (ref "U102") (pin "10") (pinfunction "COM_10") (pintype "output"))
      (node (ref "U103") (pin "10") (pinfunction "COM_10") (pintype "output"))
      (node (ref "U104") (pin "10") (pinfunction "COM_10") (pintype "output"))
    )
    (net (code "2") (name "5V") (class "Default")
      (node (ref "PCB1") (pin "5V.") (pinfunction "+5V._5V.") (pintype "bidirectional"))
      (node (ref "PCB1") (pin "5V..") (pinfunction "+5V.._5V..") (pintype "bidirectional"))
    )
    (net (code "3") (name "A0") (class "Default")
      (node (ref "PCB1") (pin "34") (pinfunction "34_34") (pintype "bidirectional"))
      (node (ref "R118") (pin "1") (pinfunction "1_1") (pintype "passive"))
    )
    (net (code "4") (name "A1") (class "Default")
      (node (ref "PCB1") (pin "35") (pinfunction "35_35") (pintype "bidirectional"))
      (node (ref "R120") (pin "1") (pinfunction "1_1") (pintype "passive"))
    )
    (net (code "5") (name "A2") (class "Default")
      (node (ref "PCB1") (pin "36") (pinfunction "36_36") (pintype "bidirectional"))
      (node (ref "R122") (pin "1") (pinfunction "1_1") (pintype "passive"))
    )
    (net (code "6") (name "A3") (class "Default")
      (node (ref "PCB1") (pin "37") (pinfunction "37_37") (pintype "bidirectional"))
      (node (ref "R124") (pin "1") (pinfunction "1_1") (pintype "passive"))
    )
    (net (code "7") (name "A4") (class "Default")
      (node (ref "PCB1") (pin "38") (pinfunction "38_38") (pintype "bidirectional"))
      (node (ref "R126") (pin "1") (pinfunction "1_1") (pintype "passive"))
    )
    (net (code "8") (name "A5") (class "Default")
      (node (ref "PCB1") (pin "39") (pinfunction "39_39") (pintype "bidirectional"))
      (node (ref "R128") (pin "1") (pinfunction "1_1") (pintype "passive"))
    )
    (net (code "9") (name "A6") (class "Default")
      (node (ref "PCB1") (pin "40") (pinfunction "40_40") (pintype "bidirectional"))
      (node (ref "R130") (pin "1") (pinfunction "1_1") (pintype "passive"))
    )
    (net (code "10") (name "A7") (class "Default")
      (node (ref "PCB1") (pin "41") (pinfunction "41_41") (pintype "bidirectional"))
      (node (ref "R132") (pin "1") (pinfunction "1_1") (pintype "passive"))
    )
    (net (code "11") (name "A8") (class "Default")
      (node (ref "PCB1") (pin "51") (pinfunction "51_51") (pintype "bidirectional"))
      (node (ref "R133") (pin "1") (pinfunction "1_1") (pintype "passive"))
    )
    (net (code "12") (name "A9") (class "Default")
      (node (ref "PCB1") (pin "50") (pinfunction "50_50") (pintype "bidirectional"))
      (node (ref "R134") (pin "1") (pinfunction "1_1") (pintype "passive"))
    )
    (net (code "13") (name "A10") (class "Default")
      (node (ref "PCB1") (pin "49") (pinfunction "49_49") (pintype "bidirectional"))
      (node (ref "R136") (pin "1") (pinfunction "1_1") (pintype "passive"))
    )
    (net (code "14") (name "A11") (class "Default")
      (node (ref "PCB1") (pin "48") (pinfunction "48_48") (pintype "bidirectional"))
      (node (ref "R138") (pin "1") (pinfunction "1_1") (pintype "passive"))
    )
    (net (code "15") (name "A12") (class "Default")
      (node (ref "PCB1") (pin "47") (pinfunction "47_47") (pintype "bidirectional"))
      (node (ref "R140") (pin "1") (pinfunction "1_1") (pintype "passive"))
    )
    (net (code "16") (name "A13") (class "Default")
      (node (ref "PCB1") (pin "46") (pinfunction "46_46") (pintype "bidirectional"))
      (node (ref "R142") (pin "1") (pinfunction "1_1") (pintype "passive"))
    )
    (net (code "17") (name "A14") (class "Default")
      (node (ref "PCB1") (pin "45") (pinfunction "45_45") (pintype "bidirectional"))
      (node (ref "R144") (pin "1") (pinfunction "1_1") (pintype "passive"))
    )
    (net (code "18") (name "A15") (class "Default")
      (node (ref "PCB1") (pin "44") (pinfunction "44_44") (pintype "bidirectional"))
      (node (ref "R147") (pin "1") (pinfunction "1_1") (pintype "passive"))
    )
    (net (code "19") (name "AREF") (class "Default")
      (node (ref "PCB1") (pin "AREF") (pinfunction "AREF_AREF") (pintype "bidirectional"))
    )
    (net (code "20") (name "AUX1_DOWN") (class "Default")
      (node (ref "PCB1") (pin "31") (pinfunction "31_31") (pintype "bidirectional"))
      (node (ref "S15") (pin "P3") (pinfunction "P3_P3") (pintype "bidirectional"))
    )
    (net (code "21") (name "AUX1_UP") (class "Default")
      (node (ref "PCB1") (pin "30") (pinfunction "30_30") (pintype "bidirectional"))
      (node (ref "S15") (pin "P1") (pinfunction "P1_P1") (pintype "bidirectional"))
    )
    (net (code "22") (name "AUX2_DOWN") (class "Default")
      (node (ref "PCB1") (pin "33") (pinfunction "33_33") (pintype "bidirectional"))
      (node (ref "S14") (pin "P3") (pinfunction "P3_P3") (pintype "bidirectional"))
    )
    (net (code "23") (name "AUX2_UP") (class "Default")
      (node (ref "PCB1") (pin "32") (pinfunction "32_32") (pintype "bidirectional"))
      (node (ref "S14") (pin "P1") (pinfunction "P1_P1") (pintype "bidirectional"))
    )
    (net (code "24") (name "CLR") (class "Default")
      (node (ref "PCB1") (pin "53") (pinfunction "53_53") (pintype "bidirectional"))
      (node (ref "S12") (pin "P3") (pinfunction "P3_P3") (pintype "bidirectional"))
    )
    (net (code "25") (name "D0") (class "Default")
      (node (ref "PCB1") (pin "25") (pinfunction "25_25") (pintype "bidirectional"))
      (node (ref "R117") (pin "1") (pinfunction "1_1") (pintype "passive"))
    )
    (net (code "26") (name "D1") (class "Default")
      (node (ref "PCB1") (pin "26") (pinfunction "26_26") (pintype "bidirectional"))
      (node (ref "R119") (pin "1") (pinfunction "1_1") (pintype "passive"))
    )
    (net (code "27") (name "D2") (class "Default")
      (node (ref "PCB1") (pin "27") (pinfunction "27_27") (pintype "bidirectional"))
      (node (ref "R121") (pin "1") (pinfunction "1_1") (pintype "passive"))
    )
    (net (code "28") (name "D3") (class "Default")
      (node (ref "PCB1") (pin "28") (pinfunction "28_28") (pintype "bidirectional"))
      (node (ref "R123") (pin "1") (pinfunction "1_1") (pintype "passive"))
    )
    (net (code "29") (name "D4") (class "Default")
      (node (ref "PCB1") (pin "14") (pinfunction "14(TX3)_14") (pintype "bidirectional"))
      (node (ref "R125") (pin "1") (pinfunction "1_1") (pintype "passive"))
    )
    (net (code "30") (name "D5") (class "Default")
      (node (ref "PCB1") (pin "15") (pinfunction "15(RX3)_15") (pintype "bidirectional"))
      (node (ref "R127") (pin "1") (pinfunction "1_1") (pintype "passive"))
    )
    (net (code "31") (name "D6") (class "Default")
      (node (ref "PCB1") (pin "29") (pinfunction "29_29") (pintype "bidirectional"))
      (node (ref "R129") (pin "1") (pinfunction "1_1") (pintype "passive"))
    )
    (net (code "32") (name "D7") (class "Default")
      (node (ref "PCB1") (pin "11") (pinfunction "11_11") (pintype "bidirectional"))
      (node (ref "R131") (pin "1") (pinfunction "1_1") (pintype "passive"))
    )
    (net (code "33") (name "DEPOSIT") (class "Default")
      (node (ref "PCB1") (pin "A4") (pinfunction "A4_A4") (pintype "bidirectional"))
      (node (ref "S11") (pin "P1") (pinfunction "P1_P1") (pintype "bidirectional"))
    )
    (net (code "34") (name "DEPOSIT_NEXT") (class "Default")
      (node (ref "PCB1") (pin "A5") (pinfunction "A5_A5") (pintype "bidirectional"))
      (node (ref "S11") (pin "P3") (pinfunction "P3_P3") (pintype "bidirectional"))
    )
    (net (code "35") (name "DUE_RESET") (class "Default")
      (node (ref "C100") (pin "+") (pinfunction "+_+") (pintype "passive"))
      (node (ref "PCB1") (pin "RESET") (pinfunction "RESET_RESET") (pintype "bidirectional"))
    )
    (net (code "36") (name "EXAMINE") (class "Default")
      (node (ref "PCB1") (pin "A2") (pinfunction "A2_A2") (pintype "bidirectional"))
      (node (ref "S10") (pin "P1") (pinfunction "P1_P1") (pintype "bidirectional"))
    )
    (net (code "37") (name "EXAMINE_NEXT") (class "Default")
      (node (ref "PCB1") (pin "A3") (pinfunction "A3_A3") (pintype "bidirectional"))
      (node (ref "S10") (pin "P3") (pinfunction "P3_P3") (pintype "bidirectional"))
    )
    (net (code "38") (name "GND") (class "Default")
      (node (ref "J100") (pin "2") (pinfunction "2_2") (pintype "passive"))
      (node (ref "J101") (pin "3") (pinfunction "3_3") (pintype "passive"))
      (node (ref "J101") (pin "7") (pinfunction "7_7") (pintype "passive"))
      (node (ref "PCB1") (pin "GND") (pinfunction "GND_GND") (pintype "bidirectional"))
      (node (ref "PCB1") (pin "GND.") (pinfunction "GND._GND.") (pintype "bidirectional"))
      (node (ref "PCB1") (pin "GND..") (pinfunction "GND.._GND..") (pintype "bidirectional"))
      (node (ref "PCB1") (pin "GND...") (pinfunction "GND..._GND...") (pintype "bidirectional"))
      (node (ref "PCB1") (pin "GND....") (pinfunction "GND...._GND....") (pintype "bidirectional"))
      (node (ref "PCB1") (pin "GND__") (pinfunction "GND___GND__") (pintype "bidirectional"))
      (node (ref "R100") (pin "1") (pinfunction "1_1") (pintype "passive"))
      (node (ref "R101") (pin "2") (pinfunction "2_2") (pintype "passive"))
      (node (ref "R102") (pin "2") (pinfunction "2_2") (pintype "passive"))
      (node (ref "R103") (pin "2") (pinfunction "2_2") (pintype "passive"))
      (node (ref "R104") (pin "2") (pinfunction "2_2") (pintype "passive"))
      (node (ref "R105") (pin "2") (pinfunction "2_2") (pintype "passive"))
      (node (ref "R106") (pin "2") (pinfunction "2_2") (pintype "passive"))
      (node (ref "R107") (pin "2") (pinfunction "2_2") (pintype "passive"))
      (node (ref "R108") (pin "2") (pinfunction "2_2") (pintype "passive"))
      (node (ref "R109") (pin "2") (pinfunction "2_2") (pintype "passive"))
      (node (ref "R110") (pin "2") (pinfunction "2_2") (pintype "passive"))
      (node (ref "R111") (pin "2") (pinfunction "2_2") (pintype "passive"))
      (node (ref "R112") (pin "2") (pinfunction "2_2") (pintype "passive"))
      (node (ref "R113") (pin "2") (pinfunction "2_2") (pintype "passive"))
      (node (ref "R114") (pin "2") (pinfunction "2_2") (pintype "passive"))
      (node (ref "R115") (pin "2") (pinfunction "2_2") (pintype "passive"))
      (node (ref "R116") (pin "2") (pinfunction "2_2") (pintype "passive"))
      (node (ref "S10") (pin "P2") (pinfunction "P2_P2") (pintype "bidirectional"))
      (node (ref "S11") (pin "P2") (pinfunction "P2_P2") (pintype "bidirectional"))
      (node (ref "S12") (pin "P2") (pinfunction "P2_P2") (pintype "bidirectional"))
      (node (ref "S13") (pin "P2") (pinfunction "P2_P2") (pintype "bidirectional"))
      (node (ref "S14") (pin "P2") (pinfunction "P2_P2") (pintype "bidirectional"))
      (node (ref "S15") (pin "P2") (pinfunction "P2_P2") (pintype "bidirectional"))
      (node (ref "S7") (pin "6") (pinfunction "6_6") (pintype "bidirectional"))
      (node (ref "S8") (pin "P2") (pinfunction "P2_P2") (pintype "bidirectional"))
      (node (ref "S9") (pin "P2") (pinfunction "P2_P2") (pintype "bidirectional"))
      (node (ref "U100") (pin "9") (pinfunction "GND_9") (pintype "passive"))
      (node (ref "U101") (pin "9") (pinfunction "GND_9") (pintype "passive"))
      (node (ref "U102") (pin "9") (pinfunction "GND_9") (pintype "passive"))
      (node (ref "U103") (pin "9") (pinfunction "GND_9") (pintype "passive"))
      (node (ref "U104") (pin "9") (pinfunction "GND_9") (pintype "passive"))
    )
    (net (code "39") (name "HLDA") (class "Default")
      (node (ref "PCB1") (pin "22") (pinfunction "22_22") (pintype "bidirectional"))
      (node (ref "R150") (pin "1") (pinfunction "1_1") (pintype "passive"))
    )
    (net (code "40") (name "HLTA") (class "Default")
      (node (ref "PCB1") (pin "5") (pinfunction "5_5") (pintype "bidirectional"))
      (node (ref "R141") (pin "1") (pinfunction "1_1") (pintype "passive"))
    )
    (net (code "41") (name "INP") (class "Default")
      (node (ref "PCB1") (pin "8") (pinfunction "8_8") (pintype "bidirectional"))
      (node (ref "R146") (pin "1") (pinfunction "1_1") (pintype "passive"))
    )
    (net (code "42") (name "INT") (class "Default")
      (node (ref "PCB1") (pin "2") (pinfunction "2_2") (pintype "bidirectional"))
      (node (ref "R135") (pin "1") (pinfunction "1_1") (pintype "passive"))
    )
    (net (code "43") (name "INTE") (class "Default")
      (node (ref "PCB1") (pin "12") (pinfunction "12_12") (pintype "bidirectional"))
      (node (ref "R151") (pin "1") (pinfunction "1_1") (pintype "passive"))
    )
    (net (code "44") (name "IOREF") (class "Default")
      (node (ref "PCB1") (pin "I/OREF") (pinfunction "IOREF_I/OREF") (pintype "bidirectional"))
    )
    (net (code "45") (name "M1") (class "Default")
      (node (ref "PCB1") (pin "7") (pinfunction "7_7") (pintype "bidirectional"))
      (node (ref "R145") (pin "1") (pinfunction "1_1") (pintype "passive"))
    )
    (net (code "46") (name "MEMR") (class "Default")
      (node (ref "PCB1") (pin "9") (pinfunction "9_9") (pintype "bidirectional"))
      (node (ref "R148") (pin "1") (pinfunction "1_1") (pintype "passive"))
    )
    (net (code "47") (name "MISO") (class "Default")
      (node (ref "J101") (pin "5") (pinfunction "5_5") (pintype "passive"))
      (node (ref "PCB1") (pin "MISO") (pinfunction "MISO_MISO") (pintype "bidirectional"))
    )
    (net (code "48") (name "MOSI") (class "Default")
      (node (ref "J101") (pin "6") (pinfunction "6_6") (pintype "passive"))
      (node (ref "PCB1") (pin "MOSI") (pinfunction "MOSI_MOSI") (pintype "bidirectional"))
    )
    (net (code "49") (name "Net-(C100-Pad-)") (class "Default")
      (node (ref "C100") (pin "-") (pinfunction "-_-") (pintype "passive"))
      (node (ref "R100") (pin "2") (pinfunction "2_2") (pintype "passive"))
    )
    (net (code "50") (name "Net-(J102-Pad1)") (class "Default")
      (node (ref "J102") (pin "1") (pinfunction "1_1") (pintype "passive"))
      (node (ref "S7") (pin "5") (pinfunction "5_5") (pintype "bidirectional"))
    )
    (net (code "51") (name "Net-(J102-Pad2)") (class "Default")
      (node (ref "J102") (pin "2") (pinfunction "2_2") (pintype "passive"))
      (node (ref "S7") (pin "2") (pinfunction "2_2") (pintype "bidirectional"))
    )
    (net (code "52") (name "Net-(LED1-PadC)") (class "Default")
      (node (ref "LED1") (pin "C") (pinfunction "C_C") (pintype "passive"))
      (node (ref "R181") (pin "2") (pinfunction "2_2") (pintype "passive"))
    )
    (net (code "53") (name "Net-(LED2-PadC)") (class "Default")
      (node (ref "LED2") (pin "C") (pinfunction "C_C") (pintype "passive"))
      (node (ref "R180") (pin "2") (pinfunction "2_2") (pintype "passive"))
    )
    (net (code "54") (name "Net-(LED3-PadC)") (class "Default")
      (node (ref "LED3") (pin "C") (pinfunction "C_C") (pintype "passive"))
      (node (ref "R178") (pin "2") (pinfunction "2_2") (pintype "passive"))
    )
    (net (code "55") (name "Net-(LED4-PadC)") (class "Default")
      (node (ref "LED4") (pin "C") (pinfunction "C_C") (pintype "passive"))
      (node (ref "R176") (pin "2") (pinfunction "2_2") (pintype "passive"))
    )
    (net (code "56") (name "Net-(LED5-PadC)") (class "Default")
      (node (ref "LED5") (pin "C") (pinfunction "C_C") (pintype "passive"))
      (node (ref "R175") (pin "2") (pinfunction "2_2") (pintype "passive"))
    )
    (net (code "57") (name "Net-(LED6-PadC)") (class "Default")
      (node (ref "LED6") (pin "C") (pinfunction "C_C") (pintype "passive"))
      (node (ref "R173") (pin "2") (pinfunction "2_2") (pintype "passive"))
    )
    (net (code "58") (name "Net-(LED7-PadC)") (class "Default")
      (node (ref "LED7") (pin "C") (pinfunction "C_C") (pintype "passive"))
      (node (ref "R171") (pin "2") (pinfunction "2_2") (pintype "passive"))
    )
    (net (code "59") (name "Net-(LED8-PadC)") (class "Default")
      (node (ref "LED8") (pin "C") (pinfunction "C_C") (pintype "passive"))
      (node (ref "R169") (pin "2") (pinfunction "2_2") (pintype "passive"))
    )
    (net (code "60") (name "Net-(LED9-PadC)") (class "Default")
      (node (ref "LED9") (pin "C") (pinfunction "C_C") (pintype "passive"))
      (node (ref "R167") (pin "2") (pinfunction "2_2") (pintype "passive"))
    )
    (net (code "61") (name "Net-(LED10-PadC)") (class "Default")
      (node (ref "LED10") (pin "C") (pinfunction "C_C") (pintype "passive"))
      (node (ref "R165") (pin "2") (pinfunction "2_2") (pintype "passive"))
    )
    (net (code "62") (name "Net-(LED11-PadC)") (class "Default")
      (node (ref "LED11") (pin "C") (pinfunction "C_C") (pintype "passive"))
      (node (ref "R161") (pin "2") (pinfunction "2_2") (pintype "passive"))
    )
    (net (code "63") (name "Net-(LED12-PadC)") (class "Default")
      (node (ref "LED12") (pin "C") (pinfunction "C_C") (pintype "passive"))
      (node (ref "R159") (pin "2") (pinfunction "2_2") (pintype "passive"))
    )
    (net (code "64") (name "Net-(LED13-PadC)") (class "Default")
      (node (ref "LED13") (pin "C") (pinfunction "C_C") (pintype "passive"))
      (node (ref "R157") (pin "2") (pinfunction "2_2") (pintype "passive"))
    )
    (net (code "65") (name "Net-(LED14-PadC)") (class "Default")
      (node (ref "LED14") (pin "C") (pinfunction "C_C") (pintype "passive"))
      (node (ref "R155") (pin "2") (pinfunction "2_2") (pintype "passive"))
    )
    (net (code "66") (name "Net-(LED15-PadC)") (class "Default")
      (node (ref "LED15") (pin "C") (pinfunction "C_C") (pintype "passive"))
      (node (ref "R153") (pin "1") (pinfunction "1_1") (pintype "passive"))
    )
    (net (code "67") (name "Net-(LED16-PadC)") (class "Default")
      (node (ref "LED16") (pin "C") (pinfunction "C_C") (pintype "passive"))
      (node (ref "R187") (pin "1") (pinfunction "1_1") (pintype "passive"))
    )
    (net (code "68") (name "Net-(LED17-PadC)") (class "Default")
      (node (ref "LED17") (pin "C") (pinfunction "C_C") (pintype "passive"))
      (node (ref "R185") (pin "1") (pinfunction "1_1") (pintype "passive"))
    )
    (net (code "69") (name "Net-(LED18-PadC)") (class "Default")
      (node (ref "LED18") (pin "C") (pinfunction "C_C") (pintype "passive"))
      (node (ref "R183") (pin "1") (pinfunction "1_1") (pintype "passive"))
    )
    (net (code "70") (name "Net-(LED19-PadC)") (class "Default")
      (node (ref "LED19") (pin "C") (pinfunction "C_C") (pintype "passive"))
      (node (ref "R182") (pin "2") (pinfunction "2_2") (pintype "passive"))
    )
    (net (code "71") (name "Net-(LED20-PadC)") (class "Default")
      (node (ref "LED20") (pin "C") (pinfunction "C_C") (pintype "passive"))
      (node (ref "R179") (pin "2") (pinfunction "2_2") (pintype "passive"))
    )
    (net (code "72") (name "Net-(LED21-PadC)") (class "Default")
      (node (ref "LED21") (pin "C") (pinfunction "C_C") (pintype "passive"))
      (node (ref "R177") (pin "2") (pinfunction "2_2") (pintype "passive"))
    )
    (net (code "73") (name "Net-(LED22-PadC)") (class "Default")
      (node (ref "LED22") (pin "C") (pinfunction "C_C") (pintype "passive"))
      (node (ref "R174") (pin "2") (pinfunction "2_2") (pintype "passive"))
    )
    (net (code "74") (name "Net-(LED23-PadC)") (class "Default")
      (node (ref "LED23") (pin "C") (pinfunction "C_C") (pintype "passive"))
      (node (ref "R172") (pin "2") (pinfunction "2_2") (pintype "passive"))
    )
    (net (code "75") (name "Net-(LED24-PadC)") (class "Default")
      (node (ref "LED24") (pin "C") (pinfunction "C_C") (pintype "passive"))
      (node (ref "R170") (pin "2") (pinfunction "2_2") (pintype "passive"))
    )
    (net (code "76") (name "Net-(LED25-PadC)") (class "Default")
      (node (ref "LED25") (pin "C") (pinfunction "C_C") (pintype "passive"))
      (node (ref "R168") (pin "2") (pinfunction "2_2") (pintype "passive"))
    )
    (net (code "77") (name "Net-(LED26-PadC)") (class "Default")
      (node (ref "LED26") (pin "C") (pinfunction "C_C") (pintype "passive"))
      (node (ref "R166") (pin "2") (pinfunction "2_2") (pintype "passive"))
    )
    (net (code "78") (name "Net-(LED27-PadC)") (class "Default")
      (node (ref "LED27") (pin "C") (pinfunction "C_C") (pintype "passive"))
      (node (ref "R164") (pin "2") (pinfunction "2_2") (pintype "passive"))
    )
    (net (code "79") (name "Net-(LED28-PadC)") (class "Default")
      (node (ref "LED28") (pin "C") (pinfunction "C_C") (pintype "passive"))
      (node (ref "R163") (pin "2") (pinfunction "2_2") (pintype "passive"))
    )
    (net (code "80") (name "Net-(LED29-PadC)") (class "Default")
      (node (ref "LED29") (pin "C") (pinfunction "C_C") (pintype "passive"))
      (node (ref "R162") (pin "2") (pinfunction "2_2") (pintype "passive"))
    )
    (net (code "81") (name "Net-(LED30-PadC)") (class "Default")
      (node (ref "LED30") (pin "C") (pinfunction "C_C") (pintype "passive"))
      (node (ref "R160") (pin "2") (pinfunction "2_2") (pintype "passive"))
    )
    (net (code "82") (name "Net-(LED31-PadC)") (class "Default")
      (node (ref "LED31") (pin "C") (pinfunction "C_C") (pintype "passive"))
      (node (ref "R158") (pin "2") (pinfunction "2_2") (pintype "passive"))
    )
    (net (code "83") (name "Net-(LED32-PadC)") (class "Default")
      (node (ref "LED32") (pin "C") (pinfunction "C_C") (pintype "passive"))
      (node (ref "R156") (pin "2") (pinfunction "2_2") (pintype "passive"))
    )
    (net (code "84") (name "Net-(LED33-PadC)") (class "Default")
      (node (ref "LED33") (pin "C") (pinfunction "C_C") (pintype "passive"))
      (node (ref "R154") (pin "1") (pinfunction "1_1") (pintype "passive"))
    )
    (net (code "85") (name "Net-(LED34-PadC)") (class "Default")
      (node (ref "LED34") (pin "C") (pinfunction "C_C") (pintype "passive"))
      (node (ref "R188") (pin "1") (pinfunction "1_1") (pintype "passive"))
    )
    (net (code "86") (name "Net-(LED35-PadC)") (class "Default")
      (node (ref "LED35") (pin "C") (pinfunction "C_C") (pintype "passive"))
      (node (ref "R186") (pin "1") (pinfunction "1_1") (pintype "passive"))
    )
    (net (code "87") (name "Net-(LED36-PadC)") (class "Default")
      (node (ref "LED36") (pin "C") (pinfunction "C_C") (pintype "passive"))
      (node (ref "R184") (pin "1") (pinfunction "1_1") (pintype "passive"))
    )
    (net (code "88") (name "Net-(U100-1B)") (class "Default")
      (node (ref "R117") (pin "2") (pinfunction "2_2") (pintype "passive"))
      (node (ref "U100") (pin "1") (pinfunction "1B_1") (pintype "input"))
    )
    (net (code "89") (name "Net-(U100-1C)") (class "Default")
      (node (ref "R183") (pin "2") (pinfunction "2_2") (pintype "passive"))
      (node (ref "U100") (pin "18") (pinfunction "1C_18") (pintype "output"))
    )
    (net (code "90") (name "Net-(U100-2B)") (class "Default")
      (node (ref "R118") (pin "2") (pinfunction "2_2") (pintype "passive"))
      (node (ref "U100") (pin "2") (pinfunction "2B_2") (pintype "input"))
    )
    (net (code "91") (name "Net-(U100-2C)") (class "Default")
      (node (ref "R184") (pin "2") (pinfunction "2_2") (pintype "passive"))
      (node (ref "U100") (pin "17") (pinfunction "2C_17") (pintype "output"))
    )
    (net (code "92") (name "Net-(U100-3B)") (class "Default")
      (node (ref "R119") (pin "2") (pinfunction "2_2") (pintype "passive"))
      (node (ref "U100") (pin "3") (pinfunction "3B_3") (pintype "input"))
    )
    (net (code "93") (name "Net-(U100-3C)") (class "Default")
      (node (ref "R185") (pin "2") (pinfunction "2_2") (pintype "passive"))
      (node (ref "U100") (pin "16") (pinfunction "3C_16") (pintype "output"))
    )
    (net (code "94") (name "Net-(U100-4B)") (class "Default")
      (node (ref "R120") (pin "2") (pinfunction "2_2") (pintype "passive"))
      (node (ref "U100") (pin "4") (pinfunction "4B_4") (pintype "input"))
    )
    (net (code "95") (name "Net-(U100-4C)") (class "Default")
      (node (ref "R186") (pin "2") (pinfunction "2_2") (pintype "passive"))
      (node (ref "U100") (pin "15") (pinfunction "4C_15") (pintype "output"))
    )
    (net (code "96") (name "Net-(U100-5B)") (class "Default")
      (node (ref "R121") (pin "2") (pinfunction "2_2") (pintype "passive"))
      (node (ref "U100") (pin "5") (pinfunction "5B_5") (pintype "input"))
    )
    (net (code "97") (name "Net-(U100-5C)") (class "Default")
      (node (ref "R187") (pin "2") (pinfunction "2_2") (pintype "passive"))
      (node (ref "U100") (pin "14") (pinfunction "5C_14") (pintype "output"))
    )
    (net (code "98") (name "Net-(U100-6B)") (class "Default")
      (node (ref "R122") (pin "2") (pinfunction "2_2") (pintype "passive"))
      (node (ref "U100") (pin "6") (pinfunction "6B_6") (pintype "input"))
    )
    (net (code "99") (name "Net-(U100-6C)") (class "Default")
      (node (ref "R188") (pin "2") (pinfunction "2_2") (pintype "passive"))
      (node (ref "U100") (pin "13") (pinfunction "6C_13") (pintype "output"))
    )
    (net (code "100") (name "Net-(U100-7B)") (class "Default")
      (node (ref "R123") (pin "2") (pinfunction "2_2") (pintype "passive"))
      (node (ref "U100") (pin "7") (pinfunction "7B_7") (pintype "input"))
    )
    (net (code "101") (name "Net-(U100-7C)") (class "Default")
      (node (ref "R153") (pin "2") (pinfunction "2_2") (pintype "passive"))
      (node (ref "U100") (pin "12") (pinfunction "7C_12") (pintype "output"))
    )
    (net (code "102") (name "Net-(U100-8B)") (class "Default")
      (node (ref "R124") (pin "2") (pinfunction "2_2") (pintype "passive"))
      (node (ref "U100") (pin "8") (pinfunction "8B_8") (pintype "input"))
    )
    (net (code "103") (name "Net-(U100-8C)") (class "Default")
      (node (ref "R154") (pin "2") (pinfunction "2_2") (pintype "passive"))
      (node (ref "U100") (pin "11") (pinfunction "8C_11") (pintype "output"))
    )
    (net (code "104") (name "Net-(U101-1B)") (class "Default")
      (node (ref "R125") (pin "2") (pinfunction "2_2") (pintype "passive"))
      (node (ref "U101") (pin "1") (pinfunction "1B_1") (pintype "input"))
    )
    (net (code "105") (name "Net-(U101-1C)") (class "Default")
      (node (ref "R155") (pin "1") (pinfunction "1_1") (pintype "passive"))
      (node (ref "U101") (pin "18") (pinfunction "1C_18") (pintype "output"))
    )
    (net (code "106") (name "Net-(U101-2B)") (class "Default")
      (node (ref "R126") (pin "2") (pinfunction "2_2") (pintype "passive"))
      (node (ref "U101") (pin "2") (pinfunction "2B_2") (pintype "input"))
    )
    (net (code "107") (name "Net-(U101-2C)") (class "Default")
      (node (ref "R156") (pin "1") (pinfunction "1_1") (pintype "passive"))
      (node (ref "U101") (pin "17") (pinfunction "2C_17") (pintype "output"))
    )
    (net (code "108") (name "Net-(U101-3B)") (class "Default")
      (node (ref "R127") (pin "2") (pinfunction "2_2") (pintype "passive"))
      (node (ref "U101") (pin "3") (pinfunction "3B_3") (pintype "input"))
    )
    (net (code "109") (name "Net-(U101-3C)") (class "Default")
      (node (ref "R157") (pin "1") (pinfunction "1_1") (pintype "passive"))
      (node (ref "U101") (pin "16") (pinfunction "3C_16") (pintype "output"))
    )
    (net (code "110") (name "Net-(U101-4B)") (class "Default")
      (node (ref "R128") (pin "2") (pinfunction "2_2") (pintype "passive"))
      (node (ref "U101") (pin "4") (pinfunction "4B_4") (pintype "input"))
    )
    (net (code "111") (name "Net-(U101-4C)") (class "Default")
      (node (ref "R158") (pin "1") (pinfunction "1_1") (pintype "passive"))
      (node (ref "U101") (pin "15") (pinfunction "4C_15") (pintype "output"))
    )
    (net (code "112") (name "Net-(U101-5B)") (class "Default")
      (node (ref "R129") (pin "2") (pinfunction "2_2") (pintype "passive"))
      (node (ref "U101") (pin "5") (pinfunction "5B_5") (pintype "input"))
    )
    (net (code "113") (name "Net-(U101-5C)") (class "Default")
      (node (ref "R159") (pin "1") (pinfunction "1_1") (pintype "passive"))
      (node (ref "U101") (pin "14") (pinfunction "5C_14") (pintype "output"))
    )
    (net (code "114") (name "Net-(U101-6B)") (class "Default")
      (node (ref "R130") (pin "2") (pinfunction "2_2") (pintype "passive"))
      (node (ref "U101") (pin "6") (pinfunction "6B_6") (pintype "input"))
    )
    (net (code "115") (name "Net-(U101-6C)") (class "Default")
      (node (ref "R160") (pin "1") (pinfunction "1_1") (pintype "passive"))
      (node (ref "U101") (pin "13") (pinfunction "6C_13") (pintype "output"))
    )
    (net (code "116") (name "Net-(U101-7B)") (class "Default")
      (node (ref "R131") (pin "2") (pinfunction "2_2") (pintype "passive"))
      (node (ref "U101") (pin "7") (pinfunction "7B_7") (pintype "input"))
    )
    (net (code "117") (name "Net-(U101-7C)") (class "Default")
      (node (ref "R161") (pin "1") (pinfunction "1_1") (pintype "passive"))
      (node (ref "U101") (pin "12") (pinfunction "7C_12") (pintype "output"))
    )
    (net (code "118") (name "Net-(U101-8B)") (class "Default")
      (node (ref "R132") (pin "2") (pinfunction "2_2") (pintype "passive"))
      (node (ref "U101") (pin "8") (pinfunction "8B_8") (pintype "input"))
    )
    (net (code "119") (name "Net-(U101-8C)") (class "Default")
      (node (ref "R162") (pin "1") (pinfunction "1_1") (pintype "passive"))
      (node (ref "U101") (pin "11") (pinfunction "8C_11") (pintype "output"))
    )
    (net (code "120") (name "Net-(U102-1B)") (class "Default")
      (node (ref "R133") (pin "2") (pinfunction "2_2") (pintype "passive"))
      (node (ref "U102") (pin "1") (pinfunction "1B_1") (pintype "input"))
    )
    (net (code "121") (name "Net-(U102-1C)") (class "Default")
      (node (ref "R163") (pin "1") (pinfunction "1_1") (pintype "passive"))
      (node (ref "U102") (pin "18") (pinfunction "1C_18") (pintype "output"))
    )
    (net (code "122") (name "Net-(U102-2B)") (class "Default")
      (node (ref "R134") (pin "2") (pinfunction "2_2") (pintype "passive"))
      (node (ref "U102") (pin "2") (pinfunction "2B_2") (pintype "input"))
    )
    (net (code "123") (name "Net-(U102-2C)") (class "Default")
      (node (ref "R164") (pin "1") (pinfunction "1_1") (pintype "passive"))
      (node (ref "U102") (pin "17") (pinfunction "2C_17") (pintype "output"))
    )
    (net (code "124") (name "Net-(U102-3B)") (class "Default")
      (node (ref "R135") (pin "2") (pinfunction "2_2") (pintype "passive"))
      (node (ref "U102") (pin "3") (pinfunction "3B_3") (pintype "input"))
    )
    (net (code "125") (name "Net-(U102-3C)") (class "Default")
      (node (ref "R165") (pin "1") (pinfunction "1_1") (pintype "passive"))
      (node (ref "U102") (pin "16") (pinfunction "3C_16") (pintype "output"))
    )
    (net (code "126") (name "Net-(U102-4B)") (class "Default")
      (node (ref "R136") (pin "2") (pinfunction "2_2") (pintype "passive"))
      (node (ref "U102") (pin "4") (pinfunction "4B_4") (pintype "input"))
    )
    (net (code "127") (name "Net-(U102-4C)") (class "Default")
      (node (ref "R166") (pin "1") (pinfunction "1_1") (pintype "passive"))
      (node (ref "U102") (pin "15") (pinfunction "4C_15") (pintype "output"))
    )
    (net (code "128") (name "Net-(U103-1B)") (class "Default")
      (node (ref "R137") (pin "2") (pinfunction "2_2") (pintype "passive"))
      (node (ref "U103") (pin "1") (pinfunction "1B_1") (pintype "input"))
    )
    (net (code "129") (name "Net-(U103-1C)") (class "Default")
      (node (ref "R167") (pin "1") (pinfunction "1_1") (pintype "passive"))
      (node (ref "U103") (pin "18") (pinfunction "1C_18") (pintype "output"))
    )
    (net (code "130") (name "Net-(U103-2B)") (class "Default")
      (node (ref "R138") (pin "2") (pinfunction "2_2") (pintype "passive"))
      (node (ref "U103") (pin "2") (pinfunction "2B_2") (pintype "input"))
    )
    (net (code "131") (name "Net-(U103-2C)") (class "Default")
      (node (ref "R168") (pin "1") (pinfunction "1_1") (pintype "passive"))
      (node (ref "U103") (pin "17") (pinfunction "2C_17") (pintype "output"))
    )
    (net (code "132") (name "Net-(U103-3B)") (class "Default")
      (node (ref "R139") (pin "2") (pinfunction "2_2") (pintype "passive"))
      (node (ref "U103") (pin "3") (pinfunction "3B_3") (pintype "input"))
    )
    (net (code "133") (name "Net-(U103-3C)") (class "Default")
      (node (ref "R169") (pin "1") (pinfunction "1_1") (pintype "passive"))
      (node (ref "U103") (pin "16") (pinfunction "3C_16") (pintype "output"))
    )
    (net (code "134") (name "Net-(U103-4B)") (class "Default")
      (node (ref "R140") (pin "2") (pinfunction "2_2") (pintype "passive"))
      (node (ref "U103") (pin "4") (pinfunction "4B_4") (pintype "input"))
    )
    (net (code "135") (name "Net-(U103-4C)") (class "Default")
      (node (ref "R170") (pin "1") (pinfunction "1_1") (pintype "passive"))
      (node (ref "U103") (pin "15") (pinfunction "4C_15") (pintype "output"))
    )
    (net (code "136") (name "Net-(U103-5B)") (class "Default")
      (node (ref "R141") (pin "2") (pinfunction "2_2") (pintype "passive"))
      (node (ref "U103") (pin "5") (pinfunction "5B_5") (pintype "input"))
    )
    (net (code "137") (name "Net-(U103-5C)") (class "Default")
      (node (ref "R171") (pin "1") (pinfunction "1_1") (pintype "passive"))
      (node (ref "U103") (pin "14") (pinfunction "5C_14") (pintype "output"))
    )
    (net (code "138") (name "Net-(U103-6B)") (class "Default")
      (node (ref "R142") (pin "2") (pinfunction "2_2") (pintype "passive"))
      (node (ref "U103") (pin "6") (pinfunction "6B_6") (pintype "input"))
    )
    (net (code "139") (name "Net-(U103-6C)") (class "Default")
      (node (ref "R172") (pin "1") (pinfunction "1_1") (pintype "passive"))
      (node (ref "U103") (pin "13") (pinfunction "6C_13") (pintype "output"))
    )
    (net (code "140") (name "Net-(U103-7B)") (class "Default")
      (node (ref "R143") (pin "2") (pinfunction "2_2") (pintype "passive"))
      (node (ref "U103") (pin "7") (pinfunction "7B_7") (pintype "input"))
    )
    (net (code "141") (name "Net-(U103-7C)") (class "Default")
      (node (ref "R173") (pin "1") (pinfunction "1_1") (pintype "passive"))
      (node (ref "U103") (pin "12") (pinfunction "7C_12") (pintype "output"))
    )
    (net (code "142") (name "Net-(U103-8B)") (class "Default")
      (node (ref "R144") (pin "2") (pinfunction "2_2") (pintype "passive"))
      (node (ref "U103") (pin "8") (pinfunction "8B_8") (pintype "input"))
    )
    (net (code "143") (name "Net-(U103-8C)") (class "Default")
      (node (ref "R174") (pin "1") (pinfunction "1_1") (pintype "passive"))
      (node (ref "U103") (pin "11") (pinfunction "8C_11") (pintype "output"))
    )
    (net (code "144") (name "Net-(U104-1B)") (class "Default")
      (node (ref "R145") (pin "2") (pinfunction "2_2") (pintype "passive"))
      (node (ref "U104") (pin "1") (pinfunction "1B_1") (pintype "input"))
    )
    (net (code "145") (name "Net-(U104-1C)") (class "Default")
      (node (ref "R175") (pin "1") (pinfunction "1_1") (pintype "passive"))
      (node (ref "U104") (pin "18") (pinfunction "1C_18") (pintype "output"))
    )
    (net (code "146") (name "Net-(U104-2B)") (class "Default")
      (node (ref "R146") (pin "2") (pinfunction "2_2") (pintype "passive"))
      (node (ref "U104") (pin "2") (pinfunction "2B_2") (pintype "input"))
    )
    (net (code "147") (name "Net-(U104-2C)") (class "Default")
      (node (ref "R176") (pin "1") (pinfunction "1_1") (pintype "passive"))
      (node (ref "U104") (pin "17") (pinfunction "2C_17") (pintype "output"))
    )
    (net (code "148") (name "Net-(U104-3B)") (class "Default")
      (node (ref "R147") (pin "2") (pinfunction "2_2") (pintype "passive"))
      (node (ref "U104") (pin "3") (pinfunction "3B_3") (pintype "input"))
    )
    (net (code "149") (name "Net-(U104-3C)") (class "Default")
      (node (ref "R177") (pin "1") (pinfunction "1_1") (pintype "passive"))
      (node (ref "U104") (pin "16") (pinfunction "3C_16") (pintype "output"))
    )
    (net (code "150") (name "Net-(U104-4B)") (class "Default")
      (node (ref "R148") (pin "2") (pinfunction "2_2") (pintype "passive"))
      (node (ref "U104") (pin "4") (pinfunction "4B_4") (pintype "input"))
    )
    (net (code "151") (name "Net-(U104-4C)") (class "Default")
      (node (ref "R178") (pin "1") (pinfunction "1_1") (pintype "passive"))
      (node (ref "U104") (pin "15") (pinfunction "4C_15") (pintype "output"))
    )
    (net (code "152") (name "Net-(U104-5B)") (class "Default")
      (node (ref "R149") (pin "2") (pinfunction "2_2") (pintype "passive"))
      (node (ref "U104") (pin "5") (pinfunction "5B_5") (pintype "input"))
    )
    (net (code "153") (name "Net-(U104-5C)") (class "Default")
      (node (ref "R179") (pin "1") (pinfunction "1_1") (pintype "passive"))
      (node (ref "U104") (pin "14") (pinfunction "5C_14") (pintype "output"))
    )
    (net (code "154") (name "Net-(U104-6B)") (class "Default")
      (node (ref "R150") (pin "2") (pinfunction "2_2") (pintype "passive"))
      (node (ref "U104") (pin "6") (pinfunction "6B_6") (pintype "input"))
    )
    (net (code "155") (name "Net-(U104-6C)") (class "Default")
      (node (ref "R180") (pin "1") (pinfunction "1_1") (pintype "passive"))
      (node (ref "U104") (pin "13") (pinfunction "6C_13") (pintype "output"))
    )
    (net (code "156") (name "Net-(U104-7B)") (class "Default")
      (node (ref "R151") (pin "2") (pinfunction "2_2") (pintype "passive"))
      (node (ref "U104") (pin "7") (pinfunction "7B_7") (pintype "input"))
    )
    (net (code "157") (name "Net-(U104-7C)") (class "Default")
      (node (ref "R181") (pin "1") (pinfunction "1_1") (pintype "passive"))
      (node (ref "U104") (pin "12") (pinfunction "7C_12") (pintype "output"))
    )
    (net (code "158") (name "Net-(U104-8B)") (class "Default")
      (node (ref "R152") (pin "2") (pinfunction "2_2") (pintype "passive"))
      (node (ref "U104") (pin "8") (pinfunction "8B_8") (pintype "input"))
    )
    (net (code "159") (name "Net-(U104-8C)") (class "Default")
      (node (ref "R182") (pin "1") (pinfunction "1_1") (pintype "passive"))
      (node (ref "U104") (pin "11") (pinfunction "8C_11") (pintype "output"))
    )
    (net (code "160") (name "OUT") (class "Default")
      (node (ref "PCB1") (pin "6") (pinfunction "6_6") (pintype "bidirectional"))
      (node (ref "R143") (pin "1") (pinfunction "1_1") (pintype "passive"))
    )
    (net (code "161") (name "PROT") (class "Default")
      (node (ref "PCB1") (pin "13") (pinfunction "13_13") (pintype "bidirectional"))
      (node (ref "R149") (pin "1") (pinfunction "1_1") (pintype "passive"))
    )
    (net (code "162") (name "PROTECT") (class "Default")
      (node (ref "PCB1") (pin "A6") (pinfunction "A6_A6") (pintype "bidirectional"))
      (node (ref "S13") (pin "P1") (pinfunction "P1_P1") (pintype "bidirectional"))
    )
    (net (code "163") (name "RESET") (class "Default")
      (node (ref "PCB1") (pin "52") (pinfunction "52_52") (pintype "bidirectional"))
      (node (ref "S12") (pin "P1") (pinfunction "P1_P1") (pintype "bidirectional"))
    )
    (net (code "164") (name "RUN") (class "Default")
      (node (ref "PCB1") (pin "20") (pinfunction "20(SDA)_20") (pintype "bidirectional"))
      (node (ref "S8") (pin "P3") (pinfunction "P3_P3") (pintype "bidirectional"))
    )
    (net (code "165") (name "SCK") (class "Default")
      (node (ref "J101") (pin "4") (pinfunction "4_4") (pintype "passive"))
      (node (ref "PCB1") (pin "SCK") (pinfunction "SCK_SCK") (pintype "bidirectional"))
    )
    (net (code "166") (name "SERIAL_RX") (class "Default")
      (node (ref "J100") (pin "3") (pinfunction "3_3") (pintype "passive"))
      (node (ref "PCB1") (pin "19") (pinfunction "19(RX1)_19") (pintype "bidirectional"))
    )
    (net (code "167") (name "SERIAL_TX") (class "Default")
      (node (ref "J100") (pin "4") (pinfunction "4_4") (pintype "passive"))
      (node (ref "PCB1") (pin "18") (pinfunction "18(TX1)_18") (pintype "bidirectional"))
    )
    (net (code "168") (name "SLOW") (class "Default")
      (node (ref "PCB1") (pin "A1") (pinfunction "A1_A1") (pintype "bidirectional"))
      (node (ref "S9") (pin "P3") (pinfunction "P3_P3") (pintype "bidirectional"))
    )
    (net (code "169") (name "STACK") (class "Default")
      (node (ref "PCB1") (pin "4") (pinfunction "4_4") (pintype "bidirectional"))
      (node (ref "R139") (pin "1") (pinfunction "1_1") (pintype "passive"))
    )
    (net (code "170") (name "STEP") (class "Default")
      (node (ref "PCB1") (pin "A0") (pinfunction "A0_A0") (pintype "bidirectional"))
      (node (ref "S9") (pin "P1") (pinfunction "P1_P1") (pintype "bidirectional"))
    )
    (net (code "171") (name "STOP") (class "Default")
      (node (ref "PCB1") (pin "21") (pinfunction "21(SCL)_21") (pintype "bidirectional"))
      (node (ref "S8") (pin "P1") (pinfunction "P1_P1") (pintype "bidirectional"))
    )
    (net (code "172") (name "SW0") (class "Default")
      (node (ref "PCB1") (pin "A8") (pinfunction "A8_A8") (pintype "bidirectional"))
      (node (ref "R101") (pin "1") (pinfunction "1_1") (pintype "passive"))
      (node (ref "S6") (pin "3") (pinfunction "3_3") (pintype "passive"))
    )
    (net (code "173") (name "SW1") (class "Default")
      (node (ref "PCB1") (pin "A9") (pinfunction "A9_A9") (pintype "bidirectional"))
      (node (ref "R102") (pin "1") (pinfunction "1_1") (pintype "passive"))
      (node (ref "S6") (pin "2") (pinfunction "2_2") (pintype "passive"))
    )
    (net (code "174") (name "SW2") (class "Default")
      (node (ref "PCB1") (pin "A10") (pinfunction "A10_A10") (pintype "bidirectional"))
      (node (ref "R103") (pin "1") (pinfunction "1_1") (pintype "passive"))
      (node (ref "S6") (pin "1") (pinfunction "1_1") (pintype "passive"))
    )
    (net (code "175") (name "SW3") (class "Default")
      (node (ref "PCB1") (pin "A11") (pinfunction "A11_A11") (pintype "bidirectional"))
      (node (ref "R104") (pin "1") (pinfunction "1_1") (pintype "passive"))
      (node (ref "S5") (pin "3") (pinfunction "3_3") (pintype "passive"))
    )
    (net (code "176") (name "SW4") (class "Default")
      (node (ref "PCB1") (pin "A12") (pinfunction "A12_A12") (pintype "bidirectional"))
      (node (ref "R105") (pin "1") (pinfunction "1_1") (pintype "passive"))
      (node (ref "S5") (pin "2") (pinfunction "2_2") (pintype "passive"))
    )
    (net (code "177") (name "SW5") (class "Default")
      (node (ref "PCB1") (pin "A13") (pinfunction "A13_A13") (pintype "bidirectional"))
      (node (ref "R106") (pin "1") (pinfunction "1_1") (pintype "passive"))
      (node (ref "S5") (pin "1") (pinfunction "1_1") (pintype "passive"))
    )
    (net (code "178") (name "SW6") (class "Default")
      (node (ref "PCB1") (pin "A14") (pinfunction "A14_A14") (pintype "bidirectional"))
      (node (ref "R107") (pin "1") (pinfunction "1_1") (pintype "passive"))
      (node (ref "S4") (pin "3") (pinfunction "3_3") (pintype "passive"))
    )
    (net (code "179") (name "SW7") (class "Default")
      (node (ref "PCB1") (pin "A15") (pinfunction "A15_A15") (pintype "bidirectional"))
      (node (ref "R108") (pin "1") (pinfunction "1_1") (pintype "passive"))
      (node (ref "S4") (pin "2") (pinfunction "2_2") (pintype "passive"))
    )
    (net (code "180") (name "SW8") (class "Default")
      (node (ref "PCB1") (pin "17") (pinfunction "17(RX2)_17") (pintype "bidirectional"))
      (node (ref "R109") (pin "1") (pinfunction "1_1") (pintype "passive"))
      (node (ref "S4") (pin "1") (pinfunction "1_1") (pintype "passive"))
    )
    (net (code "181") (name "SW9") (class "Default")
      (node (ref "PCB1") (pin "16") (pinfunction "16(TX2)_16") (pintype "bidirectional"))
      (node (ref "R110") (pin "1") (pinfunction "1_1") (pintype "passive"))
      (node (ref "S3") (pin "3") (pinfunction "3_3") (pintype "passive"))
    )
    (net (code "182") (name "SW10") (class "Default")
      (node (ref "PCB1") (pin "23") (pinfunction "23_23") (pintype "bidirectional"))
      (node (ref "R111") (pin "1") (pinfunction "1_1") (pintype "passive"))
      (node (ref "S3") (pin "2") (pinfunction "2_2") (pintype "passive"))
    )
    (net (code "183") (name "SW11") (class "Default")
      (node (ref "PCB1") (pin "24") (pinfunction "24_24") (pintype "bidirectional"))
      (node (ref "R112") (pin "1") (pinfunction "1_1") (pintype "passive"))
      (node (ref "S3") (pin "1") (pinfunction "1_1") (pintype "passive"))
    )
    (net (code "184") (name "SW12") (class "Default")
      (node (ref "PCB1") (pin "SDA1") (pinfunction "SDA1_SDA1") (pintype "bidirectional"))
      (node (ref "R113") (pin "1") (pinfunction "1_1") (pintype "passive"))
      (node (ref "S2") (pin "3") (pinfunction "3_3") (pintype "passive"))
    )
    (net (code "185") (name "SW13") (class "Default")
      (node (ref "PCB1") (pin "SCL1") (pinfunction "SCL1_SCL1") (pintype "bidirectional"))
      (node (ref "R114") (pin "1") (pinfunction "1_1") (pintype "passive"))
      (node (ref "S2") (pin "2") (pinfunction "2_2") (pintype "passive"))
    )
    (net (code "186") (name "SW14") (class "Default")
      (node (ref "PCB1") (pin "42") (pinfunction "42_42") (pintype "bidirectional"))
      (node (ref "R115") (pin "1") (pinfunction "1_1") (pintype "passive"))
      (node (ref "S2") (pin "1") (pinfunction "1_1") (pintype "passive"))
    )
    (net (code "187") (name "SW15") (class "Default")
      (node (ref "PCB1") (pin "43") (pinfunction "43_43") (pintype "bidirectional"))
      (node (ref "R116") (pin "1") (pinfunction "1_1") (pintype "passive"))
      (node (ref "S1") (pin "1") (pinfunction "1_1") (pintype "passive"))
    )
    (net (code "188") (name "UNPROTECT") (class "Default")
      (node (ref "PCB1") (pin "A7") (pinfunction "A7_A7") (pintype "bidirectional"))
      (node (ref "S13") (pin "P3") (pinfunction "P3_P3") (pintype "bidirectional"))
    )
    (net (code "189") (name "VCC") (class "Default")
      (node (ref "PCB1") (pin "3.3V") (pinfunction "3.3V_3.3V") (pintype "bidirectional"))
      (node (ref "S1") (pin "2") (pinfunction "2_2") (pintype "passive"))
      (node (ref "S2") (pin "4") (pinfunction "4_4") (pintype "passive"))
      (node (ref "S2") (pin "5") (pinfunction "5_5") (pintype "passive"))
      (node (ref "S2") (pin "6") (pinfunction "6_6") (pintype "passive"))
      (node (ref "S3") (pin "4") (pinfunction "4_4") (pintype "passive"))
      (node (ref "S3") (pin "5") (pinfunction "5_5") (pintype "passive"))
      (node (ref "S3") (pin "6") (pinfunction "6_6") (pintype "passive"))
      (node (ref "S4") (pin "4") (pinfunction "4_4") (pintype "passive"))
      (node (ref "S4") (pin "5") (pinfunction "5_5") (pintype "passive"))
      (node (ref "S4") (pin "6") (pinfunction "6_6") (pintype "passive"))
      (node (ref "S5") (pin "4") (pinfunction "4_4") (pintype "passive"))
      (node (ref "S5") (pin "5") (pinfunction "5_5") (pintype "passive"))
      (node (ref "S5") (pin "6") (pinfunction "6_6") (pintype "passive"))
      (node (ref "S6") (pin "4") (pinfunction "4_4") (pintype "passive"))
      (node (ref "S6") (pin "5") (pinfunction "5_5") (pintype "passive"))
      (node (ref "S6") (pin "6") (pinfunction "6_6") (pintype "passive"))
    )
    (net (code "190") (name "VIN") (class "Default")
      (node (ref "PCB1") (pin "VIN") (pinfunction "VIN_VIN") (pintype "bidirectional"))
      (node (ref "S7") (pin "3") (pinfunction "3_3") (pintype "bidirectional"))
    )
    (net (code "191") (name "WAIT") (class "Default")
      (node (ref "PCB1") (pin "10") (pinfunction "10_10") (pintype "bidirectional"))
      (node (ref "R152") (pin "1") (pinfunction "1_1") (pintype "passive"))
    )
    (net (code "192") (name "WO") (class "Default")
      (node (ref "PCB1") (pin "3") (pinfunction "3_3") (pintype "bidirectional"))
      (node (ref "R137") (pin "1") (pinfunction "1_1") (pintype "passive"))
    )
    (net (code "193") (name "unconnected-(J100-Pad5)") (class "Default")
      (node (ref "J100") (pin "5") (pinfunction "5_5") (pintype "passive"))
    )
    (net (code "194") (name "unconnected-(J100-Pad6)") (class "Default")
      (node (ref "J100") (pin "6") (pinfunction "6_6") (pintype "passive"))
    )
    (net (code "195") (name "unconnected-(J101-Pad2)") (class "Default")
      (node (ref "J101") (pin "2") (pinfunction "2_2") (pintype "passive"))
    )
    (net (code "196") (name "unconnected-(J101-Pad8)") (class "Default")
      (node (ref "J101") (pin "8") (pinfunction "8_8") (pintype "passive"))
    )
    (net (code "197") (name "unconnected-(PCB1-(N{slash}C)-PadN{slash}C)") (class "Default")
      (node (ref "PCB1") (pin "N/C") (pinfunction "(N/C)_N/C") (pintype "bidirectional"))
    )
    (net (code "198") (name "unconnected-(PCB1-0(RX)-Pad0)") (class "Default")
      (node (ref "PCB1") (pin "0") (pinfunction "0(RX)_0") (pintype "bidirectional"))
    )
    (net (code "199") (name "unconnected-(PCB1-1(TX)-Pad1)") (class "Default")
      (node (ref "PCB1") (pin "1") (pinfunction "1(TX)_1") (pintype "bidirectional"))
    )
    (net (code "200") (name "unconnected-(PCB1-PadRESET.)") (class "Default")
      (node (ref "PCB1") (pin "RESET.") (pinfunction "RESET._RESET.") (pintype "bidirectional"))
    )
    (net (code "201") (name "unconnected-(S7-Pad1)") (class "Default")
      (node (ref "S7") (pin "1") (pinfunction "1_1") (pintype "bidirectional"))
    )
    (net (code "202") (name "unconnected-(S7-Pad4)") (class "Default")
      (node (ref "S7") (pin "4") (pinfunction "4_4") (pintype "bidirectional"))
    )
    (net (code "203") (name "unconnected-(U102-5B-Pad5)") (class "Default")
      (node (ref "U102") (pin "5") (pinfunction "5B_5") (pintype "input"))
    )
    (net (code "204") (name "unconnected-(U102-5C-Pad14)") (class "Default")
      (node (ref "U102") (pin "14") (pinfunction "5C_14") (pintype "output"))
    )
    (net (code "205") (name "unconnected-(U102-6B-Pad6)") (class "Default")
      (node (ref "U102") (pin "6") (pinfunction "6B_6") (pintype "input"))
    )
    (net (code "206") (name "unconnected-(U102-6C-Pad13)") (class "Default")
      (node (ref "U102") (pin "13") (pinfunction "6C_13") (pintype "output"))
    )
    (net (code "207") (name "unconnected-(U102-7B-Pad7)") (class "Default")
      (node (ref "U102") (pin "7") (pinfunction "7B_7") (pintype "input"))
    )
    (net (code "208") (name "unconnected-(U102-7C-Pad12)") (class "Default")
      (node (ref "U102") (pin "12") (pinfunction "7C_12") (pintype "output"))
    )
    (net (code "209") (name "unconnected-(U102-8B-Pad8)") (class "Default")
      (node (ref "U102") (pin "8") (pinfunction "8B_8") (pintype "input"))
    )
    (net (code "210") (name "unconnected-(U102-8C-Pad11)") (class "Default")
      (node (ref "U102") (pin "11") (pinfunction "8C_11") (pintype "output"))
    )
  )
)
